# XMICRO-VDP_V1_0.net
KiCad netlist of a schematic drawn in EAGLE
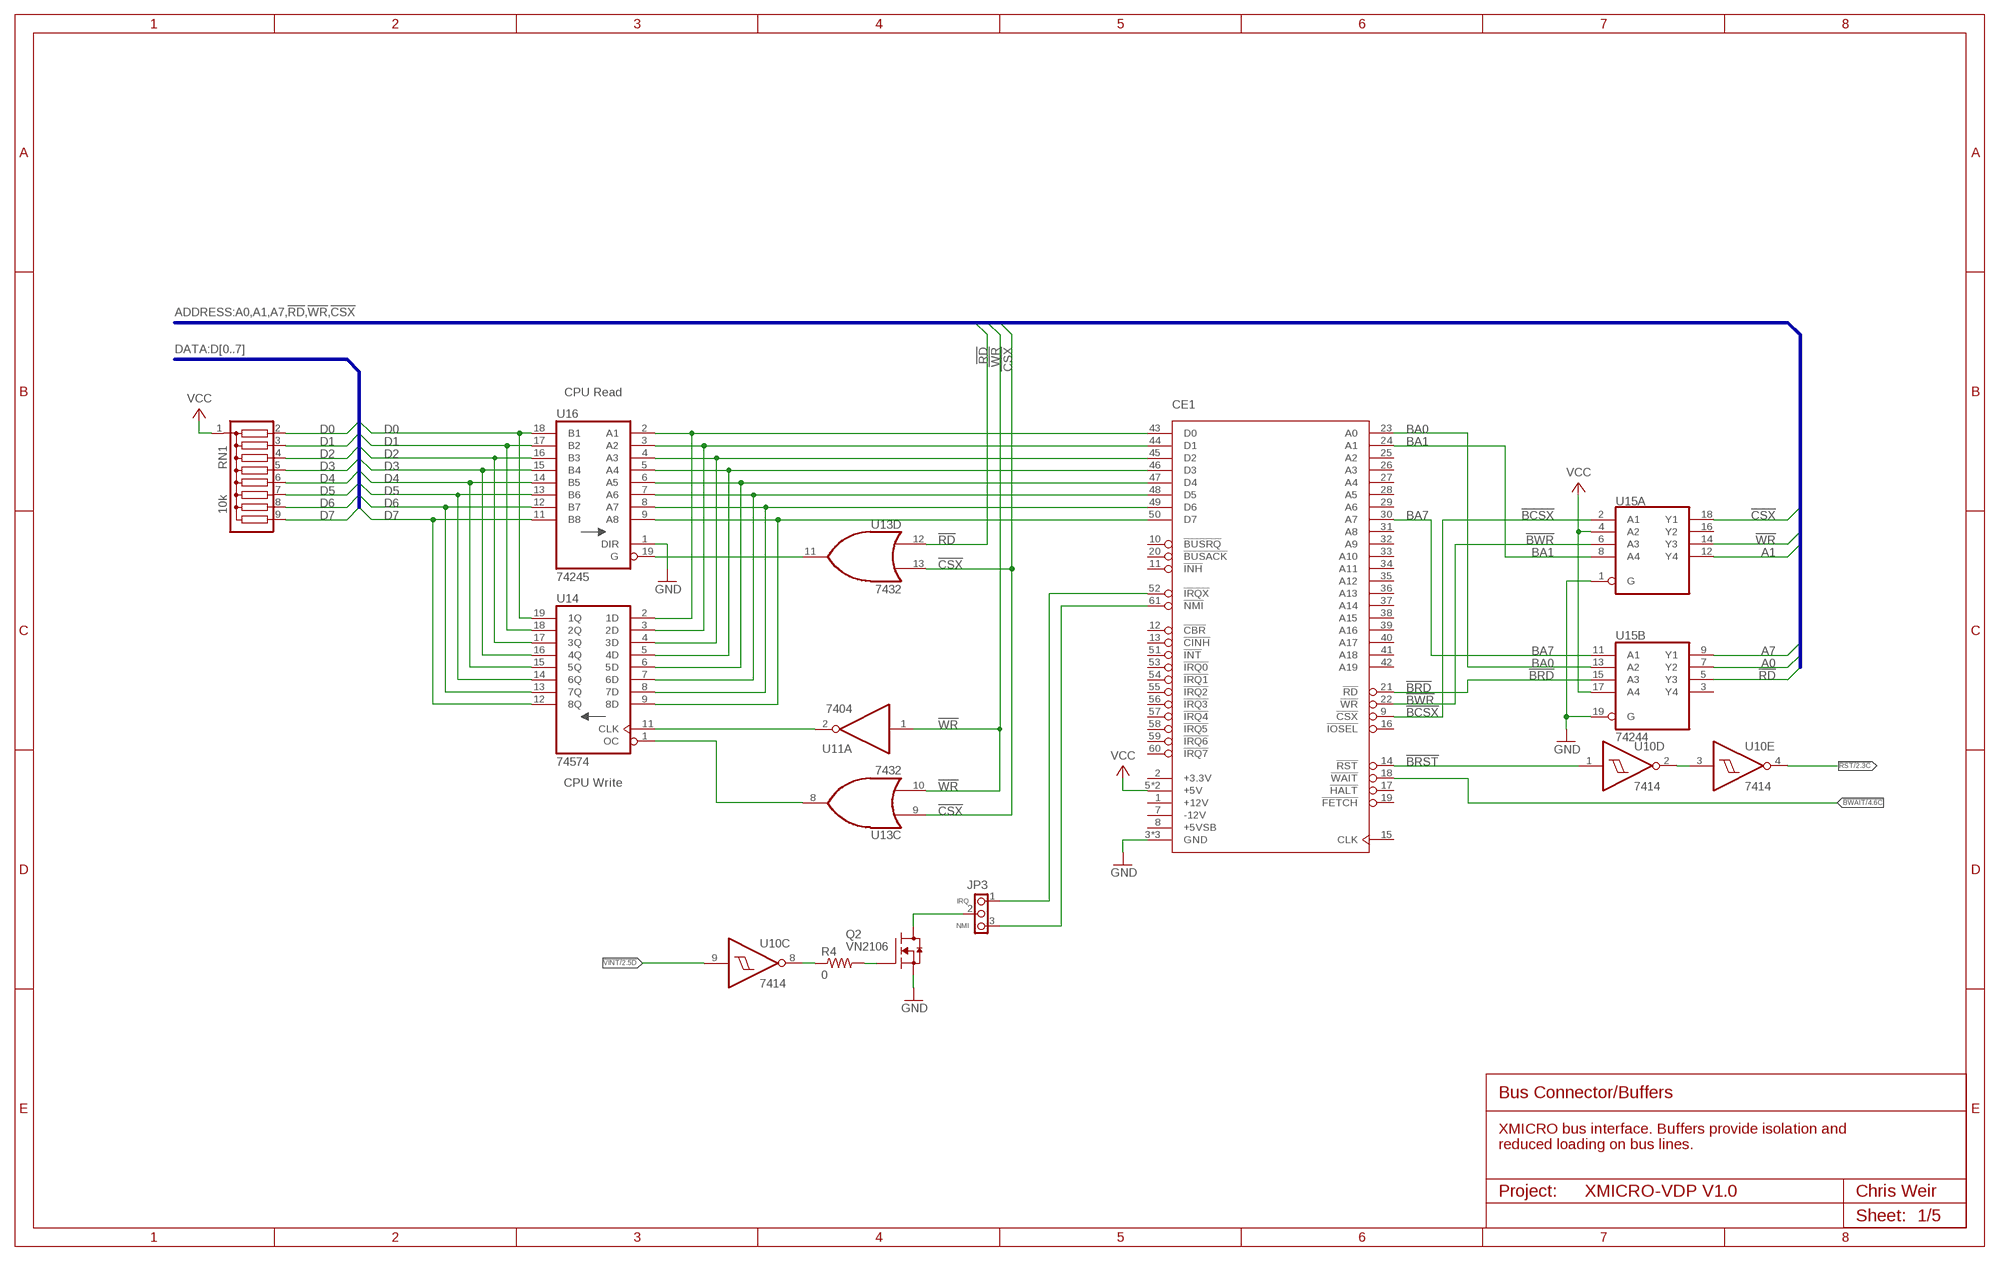
[diagram p0: schematic, sheet 1]
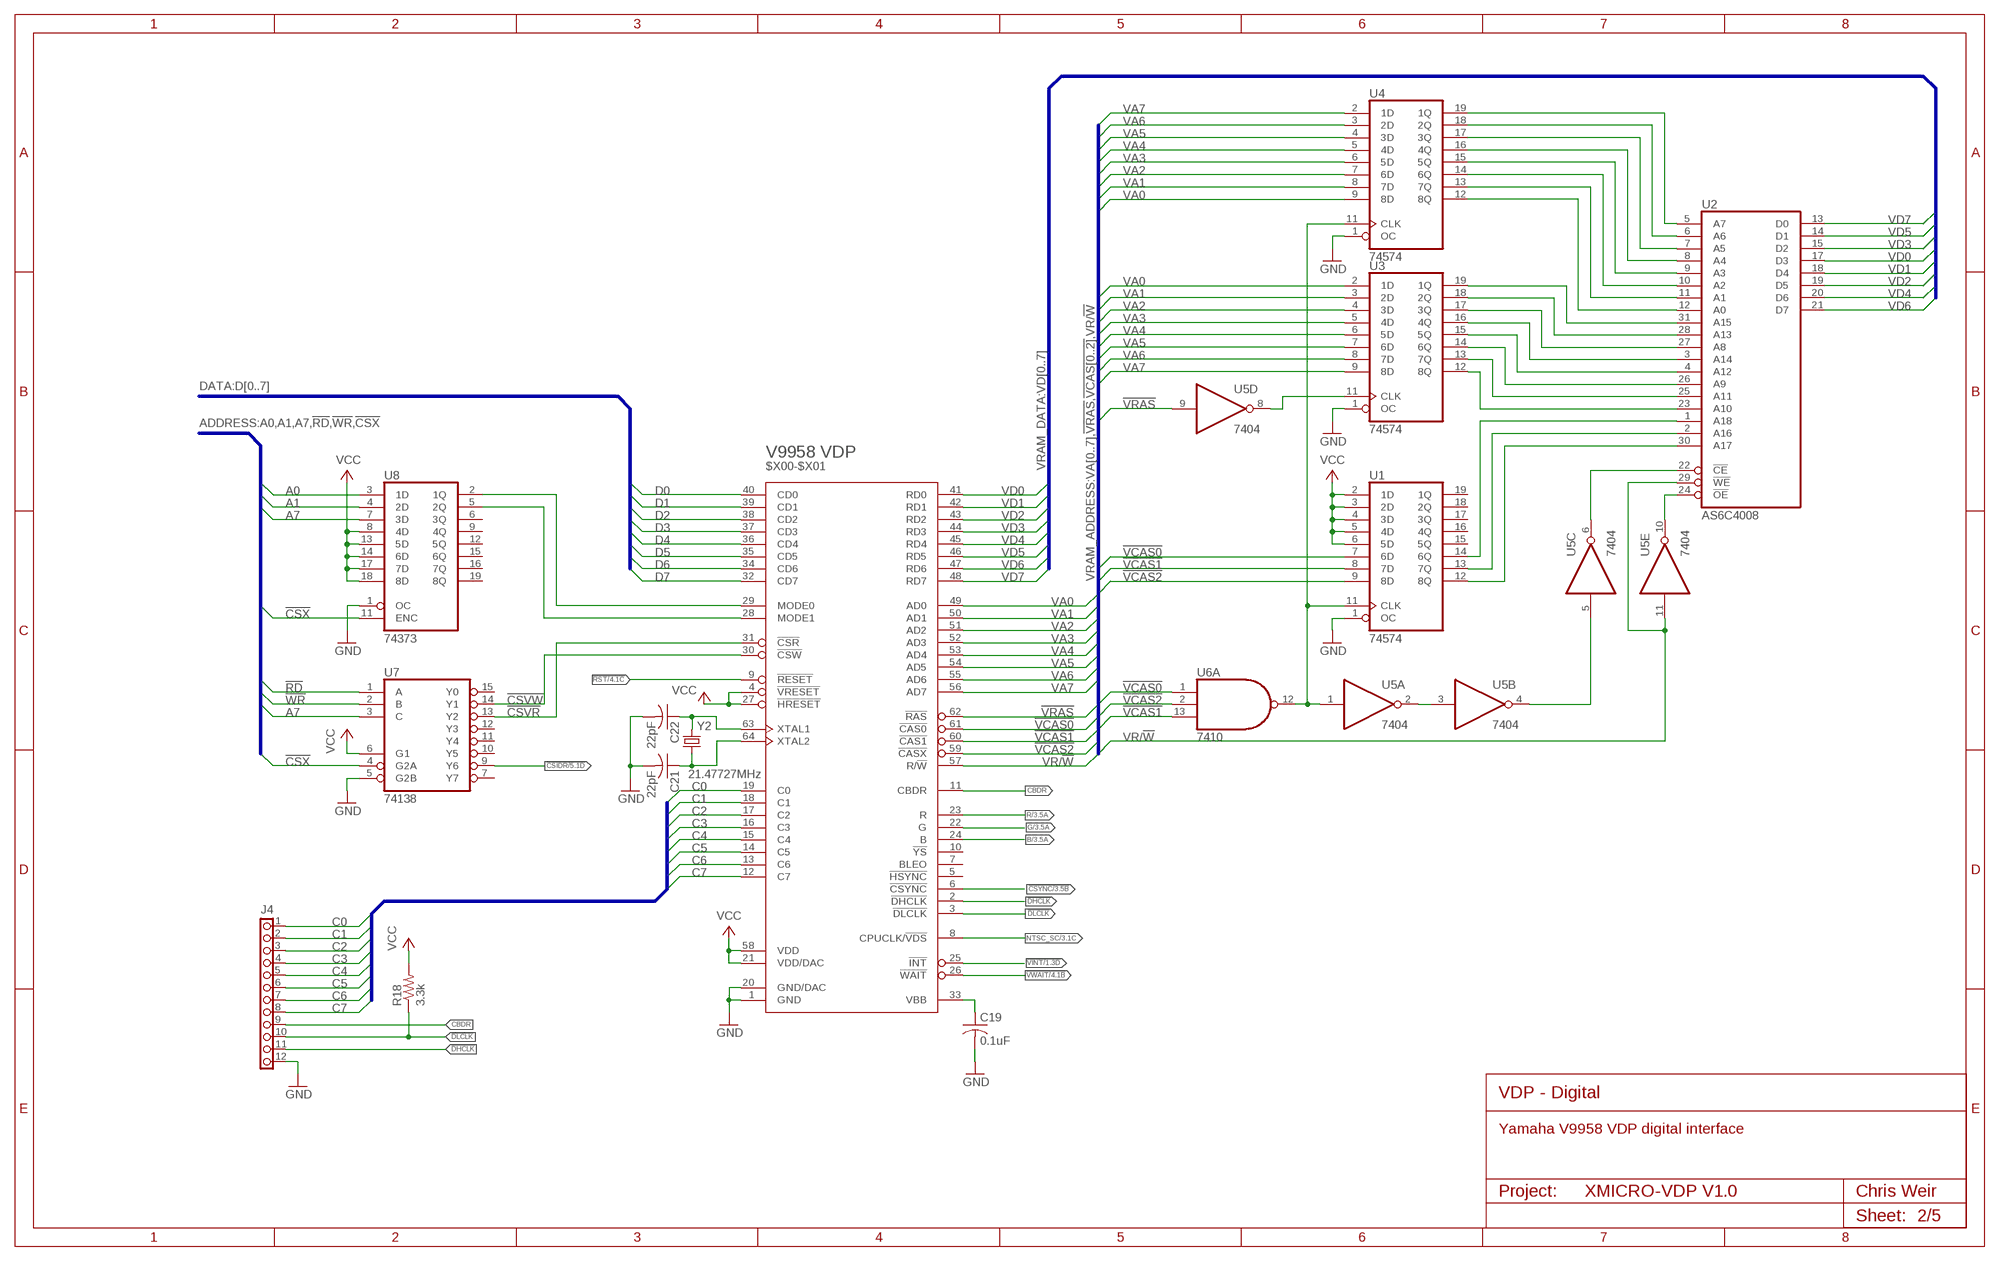
[diagram p1: schematic, sheet 2]
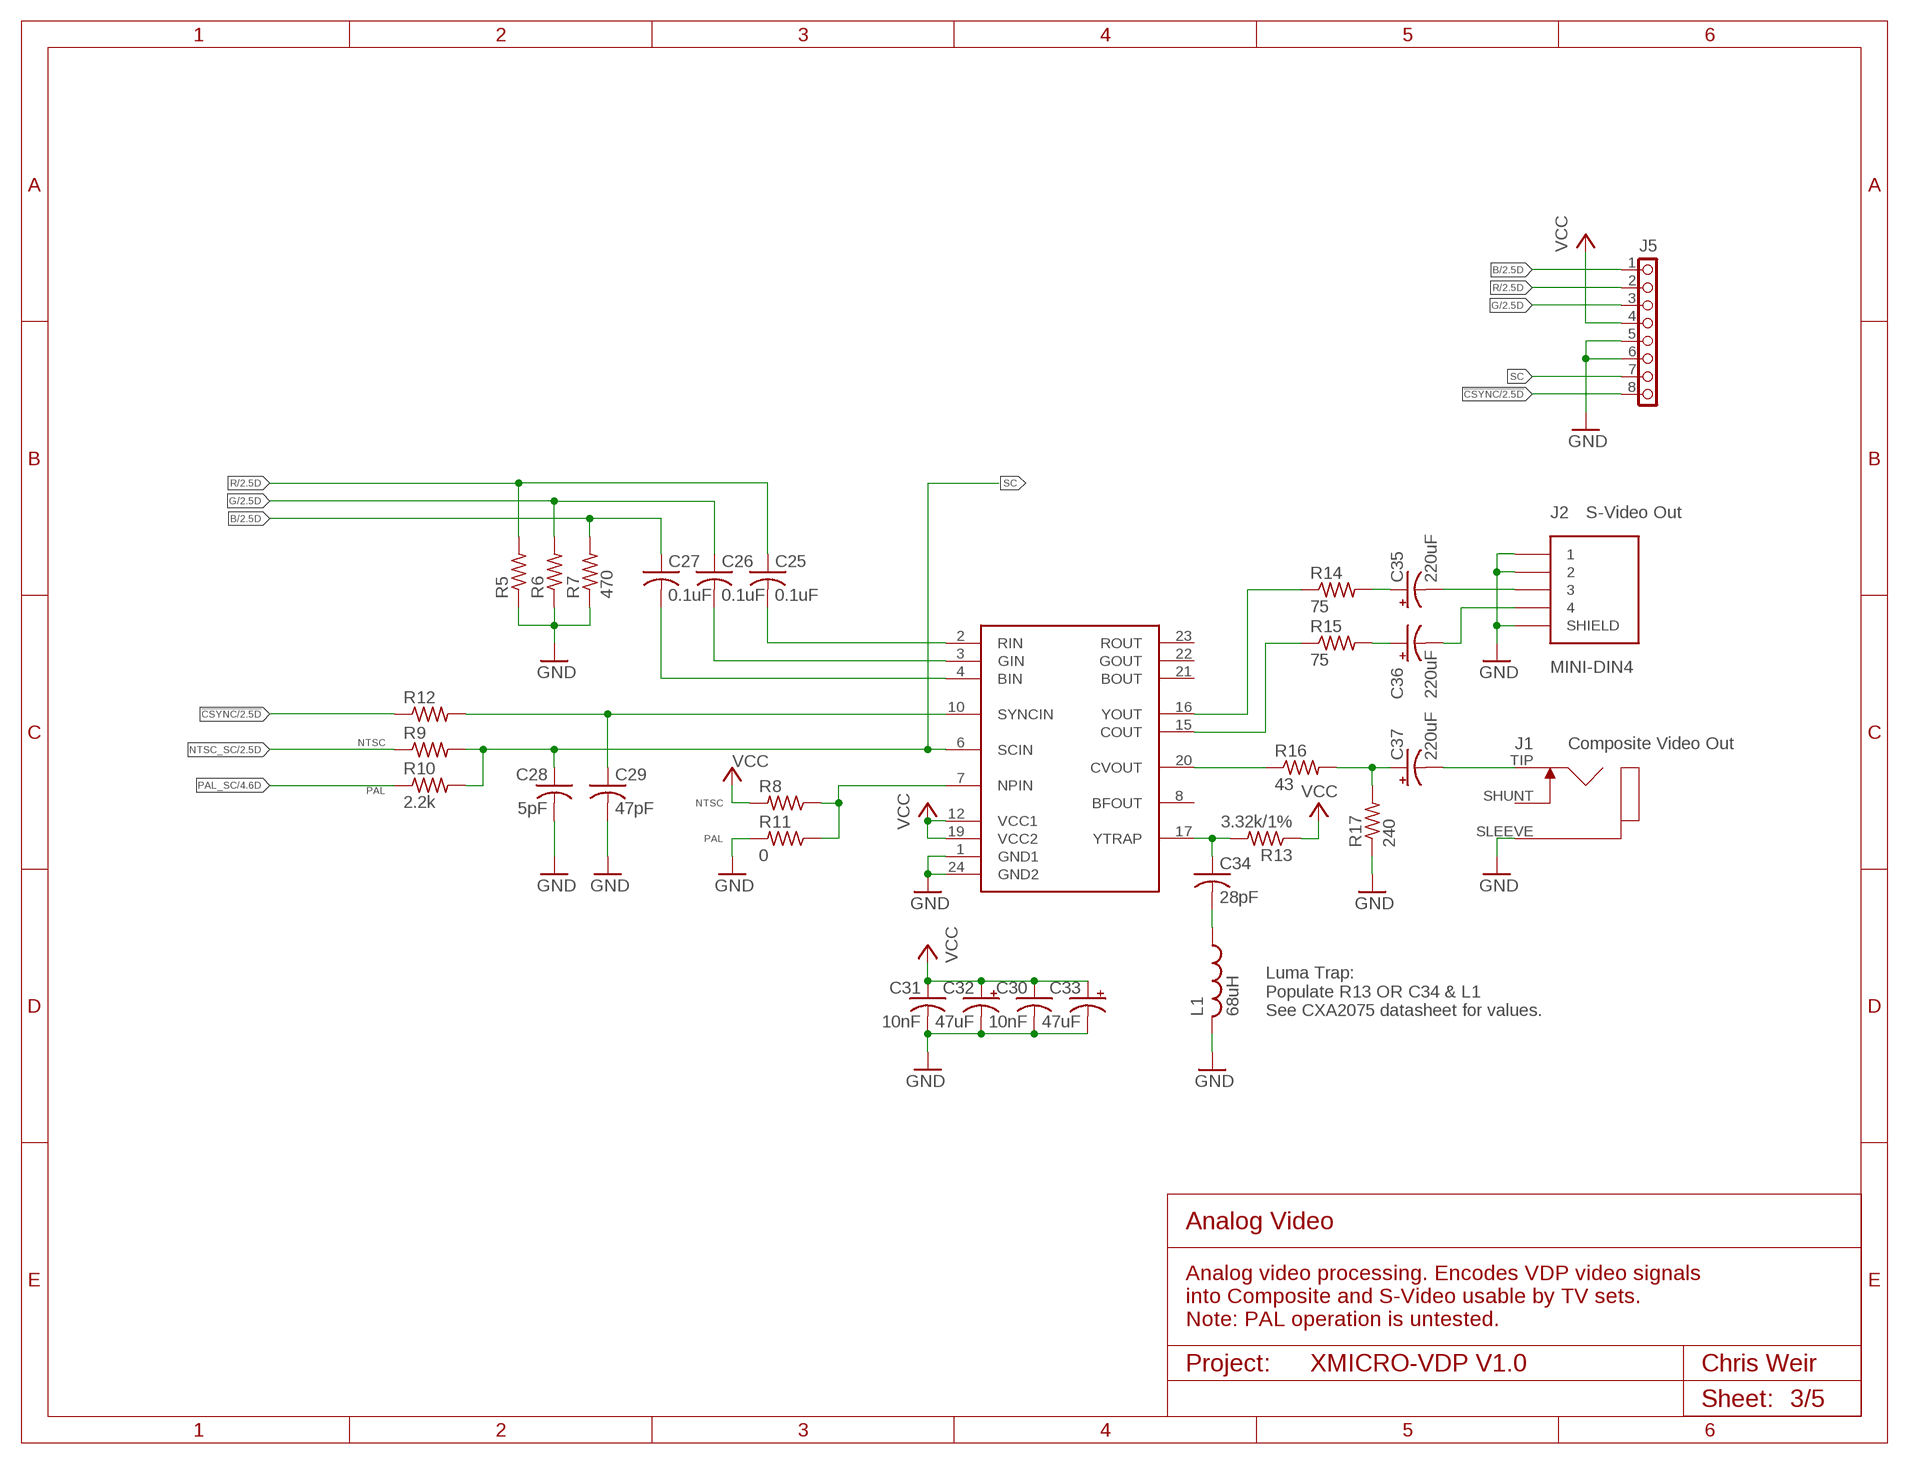
[diagram p2: schematic, sheet 3]
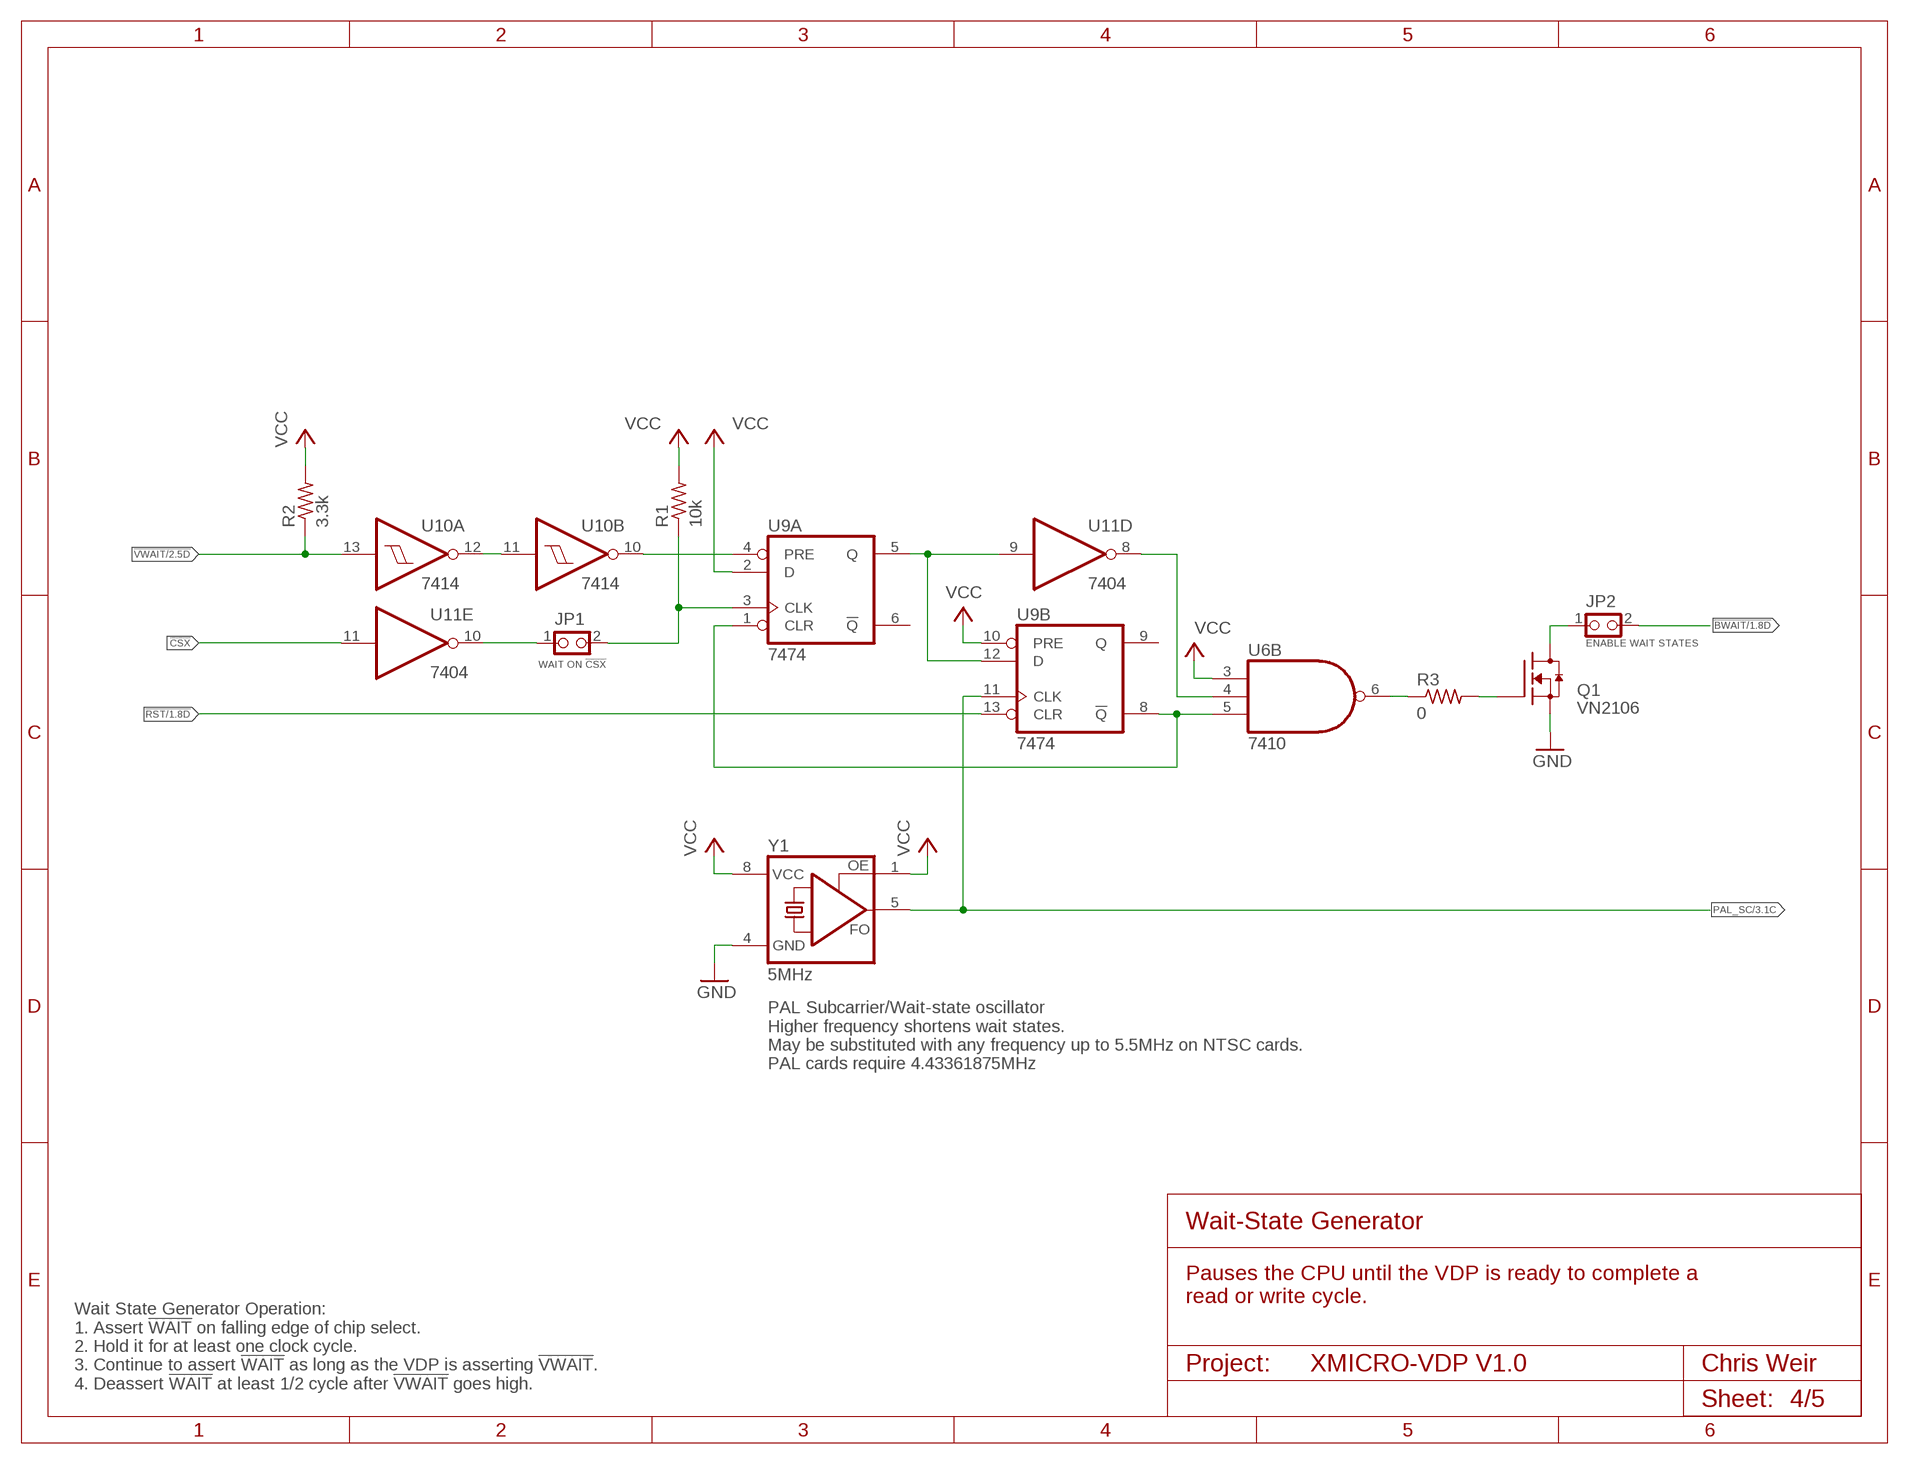
[diagram p3: schematic, sheet 4]
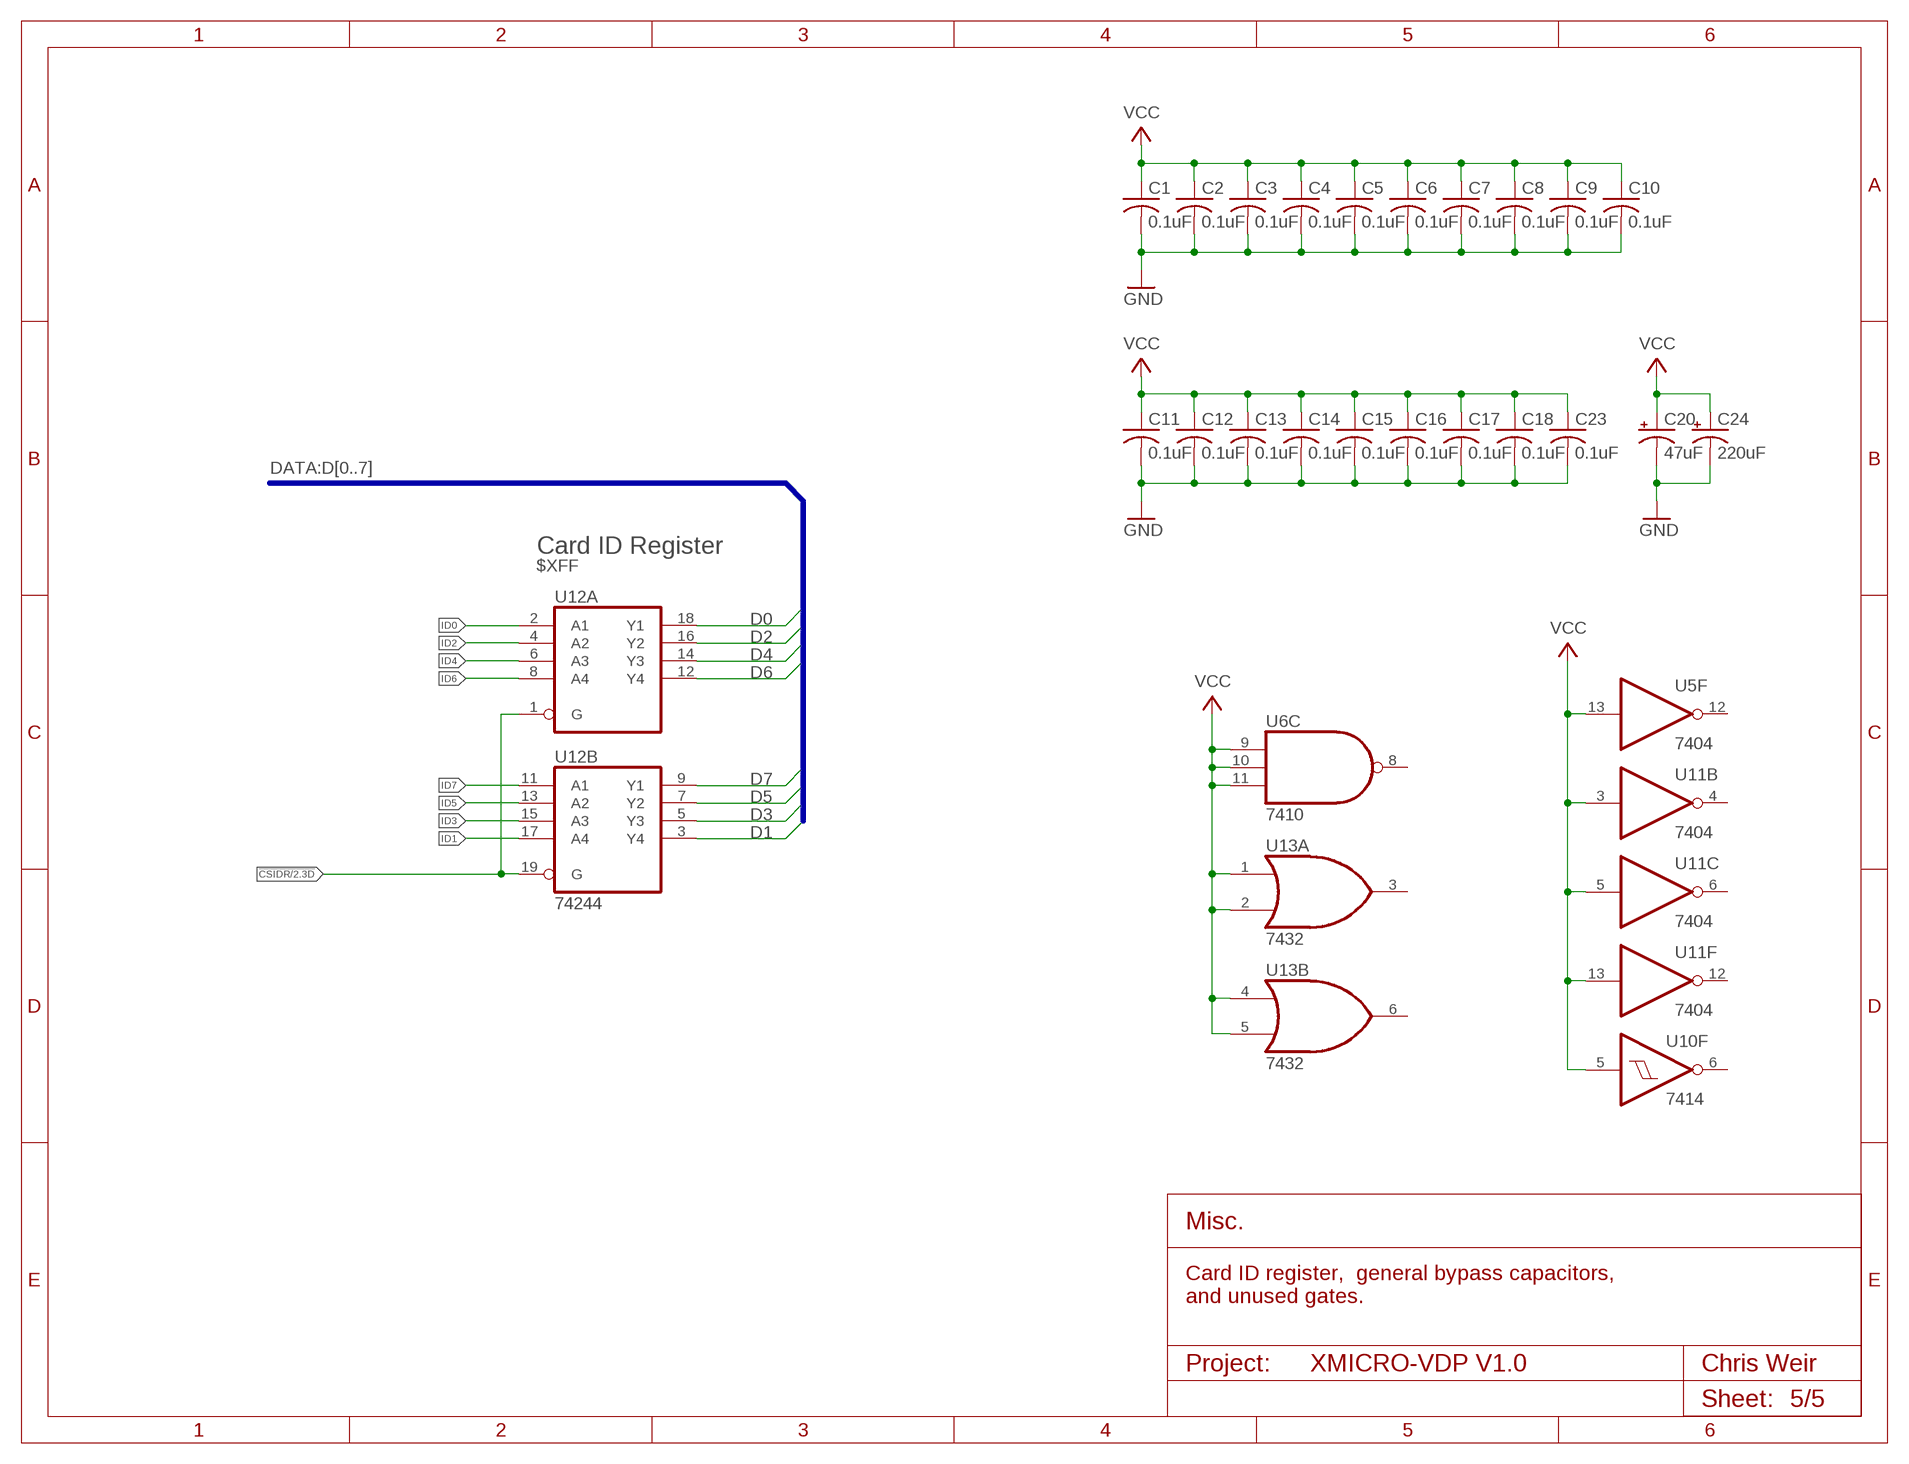
[diagram p4: schematic, sheet 5]

(export (version "E")
  (design (tool "Eeschema 10.0.6"))
  (components
    (comp (ref "JP1")
      (value "PINHD-1X2THRU")
      (footprint "eagle-import:1X02")
      (libsource (lib "eagle-import") (part "PINHD-1X2THRU"))
    )
    (comp (ref "JP2")
      (value "PINHD-1X2THRU")
      (footprint "eagle-import:1X02")
      (libsource (lib "eagle-import") (part "PINHD-1X2THRU"))
    )
    (comp (ref "Q1")
      (value "VN2106")
      (footprint "eagle-import:TO92")
      (libsource (lib "eagle-import") (part "VN2106"))
    )
    (comp (ref "R1")
      (value "10k")
      (footprint "eagle-import:0207_10")
      (libsource (lib "eagle-import") (part "R-US_0207/10"))
    )
    (comp (ref "R2")
      (value "3.3k")
      (footprint "eagle-import:0207_10")
      (libsource (lib "eagle-import") (part "R-US_0207/10"))
    )
    (comp (ref "R3")
      (value "0")
      (footprint "eagle-import:0207_10")
      (libsource (lib "eagle-import") (part "R-US_0207/10"))
    )
    (comp (ref "U6")
      (value "7410")
      (footprint "eagle-import:DIL14")
      (libsource (lib "eagle-import") (part "7410NLS"))
    )
    (comp (ref "U9")
      (value "7474")
      (footprint "eagle-import:DIL14")
      (libsource (lib "eagle-import") (part "7474NLS"))
    )
    (comp (ref "U10")
      (value "7414")
      (footprint "eagle-import:DIL14")
      (libsource (lib "eagle-import") (part "7414NLS"))
    )
    (comp (ref "U11")
      (value "7404")
      (footprint "eagle-import:DIL14")
      (libsource (lib "eagle-import") (part "7404NLS"))
    )
    (comp (ref "Y1")
      (value "5MHz")
      (footprint "eagle-import:DIL08S")
      (libsource (lib "eagle-import") (part "OSC-OE"))
    )
    (comp (ref "C19")
      (value "0.1uF")
      (footprint "eagle-import:C100")
      (libsource (lib "eagle-import") (part "C-US100"))
    )
    (comp (ref "C21")
      (value "22pF")
      (footprint "eagle-import:C100")
      (libsource (lib "eagle-import") (part "C-US100"))
    )
    (comp (ref "C22")
      (value "22pF")
      (footprint "eagle-import:C100")
      (libsource (lib "eagle-import") (part "C-US100"))
    )
    (comp (ref "J4")
      (value "PINHD-2X6")
      (footprint "eagle-import:2X06")
      (libsource (lib "eagle-import") (part "PINHD-2X6"))
    )
    (comp (ref "R18")
      (value "3.3k")
      (footprint "eagle-import:0207_10")
      (libsource (lib "eagle-import") (part "R-US_0207/10"))
    )
    (comp (ref "U1")
      (value "74574")
      (footprint "eagle-import:DIL20")
      (libsource (lib "eagle-import") (part "74574NHC"))
    )
    (comp (ref "U2")
      (value "AS6C4008")
      (footprint "eagle-import:DIL32-6")
      (libsource (lib "eagle-import") (part "4008-VDP"))
    )
    (comp (ref "U3")
      (value "74574")
      (footprint "eagle-import:DIL20")
      (libsource (lib "eagle-import") (part "74574NHC"))
    )
    (comp (ref "U4")
      (value "74574")
      (footprint "eagle-import:DIL20")
      (libsource (lib "eagle-import") (part "74574NHC"))
    )
    (comp (ref "U5")
      (value "7404")
      (footprint "eagle-import:DIL14")
      (libsource (lib "eagle-import") (part "7404NLS"))
    )
    (comp (ref "U7")
      (value "74138")
      (footprint "eagle-import:DIL16")
      (libsource (lib "eagle-import") (part "74138NS"))
    )
    (comp (ref "U8")
      (value "74373")
      (footprint "eagle-import:DIL20")
      (libsource (lib "eagle-import") (part "74373NLS"))
    )
    (comp (ref "U17")
      (value "V9958")
      (footprint "eagle-import:SDIP64")
      (libsource (lib "eagle-import") (part "V9958"))
    )
    (comp (ref "Y2")
      (value "21.47727MHz")
      (footprint "eagle-import:HC-49US")
      (libsource (lib "eagle-import") (part "CRYSTAL"))
    )
    (comp (ref "C1")
      (value "0.1uF")
      (footprint "eagle-import:C100")
      (libsource (lib "eagle-import") (part "C-US100"))
    )
    (comp (ref "C2")
      (value "0.1uF")
      (footprint "eagle-import:C100")
      (libsource (lib "eagle-import") (part "C-US100"))
    )
    (comp (ref "C3")
      (value "0.1uF")
      (footprint "eagle-import:C100")
      (libsource (lib "eagle-import") (part "C-US100"))
    )
    (comp (ref "C4")
      (value "0.1uF")
      (footprint "eagle-import:C100")
      (libsource (lib "eagle-import") (part "C-US100"))
    )
    (comp (ref "C5")
      (value "0.1uF")
      (footprint "eagle-import:C100")
      (libsource (lib "eagle-import") (part "C-US100"))
    )
    (comp (ref "C6")
      (value "0.1uF")
      (footprint "eagle-import:C100")
      (libsource (lib "eagle-import") (part "C-US100"))
    )
    (comp (ref "C7")
      (value "0.1uF")
      (footprint "eagle-import:C100")
      (libsource (lib "eagle-import") (part "C-US100"))
    )
    (comp (ref "C8")
      (value "0.1uF")
      (footprint "eagle-import:C100")
      (libsource (lib "eagle-import") (part "C-US100"))
    )
    (comp (ref "C9")
      (value "0.1uF")
      (footprint "eagle-import:C100")
      (libsource (lib "eagle-import") (part "C-US100"))
    )
    (comp (ref "C10")
      (value "0.1uF")
      (footprint "eagle-import:C100")
      (libsource (lib "eagle-import") (part "C-US100"))
    )
    (comp (ref "C11")
      (value "0.1uF")
      (footprint "eagle-import:C100")
      (libsource (lib "eagle-import") (part "C-US100"))
    )
    (comp (ref "C12")
      (value "0.1uF")
      (footprint "eagle-import:C100")
      (libsource (lib "eagle-import") (part "C-US100"))
    )
    (comp (ref "C13")
      (value "0.1uF")
      (footprint "eagle-import:C100")
      (libsource (lib "eagle-import") (part "C-US100"))
    )
    (comp (ref "C14")
      (value "0.1uF")
      (footprint "eagle-import:C100")
      (libsource (lib "eagle-import") (part "C-US100"))
    )
    (comp (ref "C15")
      (value "0.1uF")
      (footprint "eagle-import:C100")
      (libsource (lib "eagle-import") (part "C-US100"))
    )
    (comp (ref "C16")
      (value "0.1uF")
      (footprint "eagle-import:C100")
      (libsource (lib "eagle-import") (part "C-US100"))
    )
    (comp (ref "C17")
      (value "0.1uF")
      (footprint "eagle-import:C100")
      (libsource (lib "eagle-import") (part "C-US100"))
    )
    (comp (ref "C18")
      (value "0.1uF")
      (footprint "eagle-import:C100")
      (libsource (lib "eagle-import") (part "C-US100"))
    )
    (comp (ref "C20")
      (value "47uF")
      (footprint "eagle-import:E2,5-6")
      (libsource (lib "eagle-import") (part "CPOL-USE2.5-6"))
    )
    (comp (ref "C23")
      (value "0.1uF")
      (footprint "eagle-import:C100")
      (libsource (lib "eagle-import") (part "C-US100"))
    )
    (comp (ref "C24")
      (value "220uF")
      (footprint "eagle-import:C-10-5")
      (libsource (lib "eagle-import") (part "CPOL-US-10-5"))
    )
    (comp (ref "U12")
      (value "74244")
      (footprint "eagle-import:DIL20")
      (libsource (lib "eagle-import") (part "74244NLS"))
    )
    (comp (ref "U13")
      (value "7432")
      (footprint "eagle-import:DIL14")
      (libsource (lib "eagle-import") (part "7432NLS"))
    )
    (comp (ref "C25")
      (value "0.1uF")
      (footprint "eagle-import:C100")
      (libsource (lib "eagle-import") (part "C-US100"))
    )
    (comp (ref "C26")
      (value "0.1uF")
      (footprint "eagle-import:C100")
      (libsource (lib "eagle-import") (part "C-US100"))
    )
    (comp (ref "C27")
      (value "0.1uF")
      (footprint "eagle-import:C100")
      (libsource (lib "eagle-import") (part "C-US100"))
    )
    (comp (ref "C28")
      (value "5pF")
      (footprint "eagle-import:C100")
      (libsource (lib "eagle-import") (part "C-US100"))
    )
    (comp (ref "C29")
      (value "47pF")
      (footprint "eagle-import:C100")
      (libsource (lib "eagle-import") (part "C-US100"))
    )
    (comp (ref "C30")
      (value "10nF")
      (footprint "eagle-import:C100")
      (libsource (lib "eagle-import") (part "C-US100"))
    )
    (comp (ref "C31")
      (value "10nF")
      (footprint "eagle-import:C100")
      (libsource (lib "eagle-import") (part "C-US100"))
    )
    (comp (ref "C32")
      (value "47uF")
      (footprint "eagle-import:E2,5-6")
      (libsource (lib "eagle-import") (part "CPOL-USE2.5-6"))
    )
    (comp (ref "C33")
      (value "47uF")
      (footprint "eagle-import:E2,5-6")
      (libsource (lib "eagle-import") (part "CPOL-USE2.5-6"))
    )
    (comp (ref "C34")
      (value "28pF")
      (footprint "eagle-import:C100")
      (libsource (lib "eagle-import") (part "C-US100"))
    )
    (comp (ref "C35")
      (value "220uF")
      (footprint "eagle-import:E2,5-6")
      (libsource (lib "eagle-import") (part "CPOL-USE2.5-6"))
    )
    (comp (ref "C36")
      (value "220uF")
      (footprint "eagle-import:E2,5-6")
      (libsource (lib "eagle-import") (part "CPOL-USE2.5-6"))
    )
    (comp (ref "C37")
      (value "220uF")
      (footprint "eagle-import:E2,5-6")
      (libsource (lib "eagle-import") (part "CPOL-USE2.5-6"))
    )
    (comp (ref "J1")
      (value "PJRAN1XU04AUX")
      (footprint "eagle-import:PJRAN1")
      (libsource (lib "eagle-import") (part "PJRAN1"))
    )
    (comp (ref "J2")
      (value "MINI-DIN4")
      (footprint "eagle-import:MINI-DIN4")
      (libsource (lib "eagle-import") (part "MINI-DIN4"))
    )
    (comp (ref "J5")
      (value "PINHD-1X8")
      (footprint "eagle-import:1X08")
      (libsource (lib "eagle-import") (part "PINHD-1X8"))
    )
    (comp (ref "L1")
      (value "68uH")
      (footprint "eagle-import:0204V")
      (libsource (lib "eagle-import") (part "L-US0204V"))
    )
    (comp (ref "R5")
      (value "470")
      (footprint "eagle-import:0207_10")
      (libsource (lib "eagle-import") (part "R-US_0207/10"))
    )
    (comp (ref "R6")
      (value "470")
      (footprint "eagle-import:0207_10")
      (libsource (lib "eagle-import") (part "R-US_0207/10"))
    )
    (comp (ref "R7")
      (value "470")
      (footprint "eagle-import:0207_10")
      (libsource (lib "eagle-import") (part "R-US_0207/10"))
    )
    (comp (ref "R8")
      (value "0")
      (footprint "eagle-import:0207_10")
      (libsource (lib "eagle-import") (part "R-US_0207/10"))
    )
    (comp (ref "R9")
      (value "2.2k")
      (footprint "eagle-import:0207_10")
      (libsource (lib "eagle-import") (part "R-US_0207/10"))
    )
    (comp (ref "R10")
      (value "2.2k")
      (footprint "eagle-import:0207_10")
      (libsource (lib "eagle-import") (part "R-US_0207/10"))
    )
    (comp (ref "R11")
      (value "0")
      (footprint "eagle-import:0207_10")
      (libsource (lib "eagle-import") (part "R-US_0207/10"))
    )
    (comp (ref "R12")
      (value "2.2k")
      (footprint "eagle-import:0207_10")
      (libsource (lib "eagle-import") (part "R-US_0207/10"))
    )
    (comp (ref "R13")
      (value "3.32k/1%")
      (footprint "eagle-import:0207_10")
      (libsource (lib "eagle-import") (part "R-US_0207/10"))
    )
    (comp (ref "R14")
      (value "75")
      (footprint "eagle-import:0207_10")
      (libsource (lib "eagle-import") (part "R-US_0207/10"))
    )
    (comp (ref "R15")
      (value "75")
      (footprint "eagle-import:0207_10")
      (libsource (lib "eagle-import") (part "R-US_0207/10"))
    )
    (comp (ref "R16")
      (value "43")
      (footprint "eagle-import:0207_10")
      (libsource (lib "eagle-import") (part "R-US_0207/10"))
    )
    (comp (ref "R17")
      (value "240")
      (footprint "eagle-import:0207_10")
      (libsource (lib "eagle-import") (part "R-US_0207/10"))
    )
    (comp (ref "U18")
      (value "CXA2075")
      (footprint "eagle-import:SOP-24")
      (libsource (lib "eagle-import") (part "CXA2075"))
    )
    (comp (ref "CE1")
      (value "XMICRO-BUS-EDGE62M")
      (footprint "eagle-import:EDGE62M")
      (libsource (lib "eagle-import") (part "XMICRO-BUS-EDGE62M"))
    )
    (comp (ref "JP3")
      (value "PINHD1X3THRU")
      (footprint "eagle-import:1X03")
      (libsource (lib "eagle-import") (part "PINHD1X3THRU"))
    )
    (comp (ref "Q2")
      (value "VN2106")
      (footprint "eagle-import:TO92")
      (libsource (lib "eagle-import") (part "VN2106"))
    )
    (comp (ref "R4")
      (value "0")
      (footprint "eagle-import:0207_10")
      (libsource (lib "eagle-import") (part "R-US_0207/10"))
    )
    (comp (ref "RN1")
      (value "10k")
      (footprint "eagle-import:SIL9")
      (libsource (lib "eagle-import") (part "RN8"))
    )
    (comp (ref "U14")
      (value "74574")
      (footprint "eagle-import:DIL20")
      (libsource (lib "eagle-import") (part "74574NHC"))
    )
    (comp (ref "U15")
      (value "74244")
      (footprint "eagle-import:DIL20")
      (libsource (lib "eagle-import") (part "74244NLS"))
    )
    (comp (ref "U16")
      (value "74245")
      (footprint "eagle-import:DIL20")
      (libsource (lib "eagle-import") (part "74245NLS"))
    )
  )
  (nets
    (net (code "42") (name "A0") (class "Default")
      (node (ref "U15") (pin "7") (pinfunction "Y2_7") (pintype "tri_state"))
      (node (ref "U8") (pin "3") (pinfunction "1D_3") (pintype "input"))
    )
    (net (code "43") (name "A1") (class "Default")
      (node (ref "U15") (pin "12") (pinfunction "Y4_12") (pintype "tri_state"))
      (node (ref "U8") (pin "4") (pinfunction "2D_4") (pintype "input"))
    )
    (net (code "44") (name "A7") (class "Default")
      (node (ref "U15") (pin "9") (pinfunction "Y1_9") (pintype "tri_state"))
      (node (ref "U7") (pin "3") (pinfunction "C_3") (pintype "input"))
      (node (ref "U8") (pin "7") (pinfunction "3D_7") (pintype "input"))
    )
    (net (code "45") (name "B") (class "Default")
      (node (ref "C27") (pin "P$1") (pinfunction "1_P$1") (pintype "passive"))
      (node (ref "J5") (pin "1") (pinfunction "1_1") (pintype "passive"))
      (node (ref "R7") (pin "2") (pinfunction "2_2") (pintype "passive"))
      (node (ref "U17") (pin "24") (pinfunction "B_24") (pintype "output"))
    )
    (net (code "46") (name "BA0") (class "Default")
      (node (ref "CE1") (pin "23") (pinfunction "A0_23") (pintype "bidirectional"))
      (node (ref "U15") (pin "13") (pinfunction "A2_13") (pintype "input"))
    )
    (net (code "47") (name "BA1") (class "Default")
      (node (ref "CE1") (pin "24") (pinfunction "A1_24") (pintype "bidirectional"))
      (node (ref "U15") (pin "8") (pinfunction "A4_8") (pintype "input"))
    )
    (net (code "48") (name "BA7") (class "Default")
      (node (ref "CE1") (pin "30") (pinfunction "A7_30") (pintype "bidirectional"))
      (node (ref "U15") (pin "11") (pinfunction "A1_11") (pintype "input"))
    )
    (net (code "49") (name "C0") (class "Default")
      (node (ref "J4") (pin "1") (pinfunction "1_1") (pintype "passive"))
      (node (ref "U17") (pin "19") (pinfunction "C0_19") (pintype "bidirectional"))
    )
    (net (code "50") (name "C1") (class "Default")
      (node (ref "J4") (pin "2") (pinfunction "2_2") (pintype "passive"))
      (node (ref "U17") (pin "18") (pinfunction "C1_18") (pintype "bidirectional"))
    )
    (net (code "51") (name "C2") (class "Default")
      (node (ref "J4") (pin "3") (pinfunction "3_3") (pintype "passive"))
      (node (ref "U17") (pin "17") (pinfunction "C2_17") (pintype "bidirectional"))
    )
    (net (code "52") (name "C3") (class "Default")
      (node (ref "J4") (pin "4") (pinfunction "4_4") (pintype "passive"))
      (node (ref "U17") (pin "16") (pinfunction "C3_16") (pintype "bidirectional"))
    )
    (net (code "53") (name "C4") (class "Default")
      (node (ref "J4") (pin "5") (pinfunction "5_5") (pintype "passive"))
      (node (ref "U17") (pin "15") (pinfunction "C4_15") (pintype "bidirectional"))
    )
    (net (code "54") (name "C5") (class "Default")
      (node (ref "J4") (pin "6") (pinfunction "6_6") (pintype "passive"))
      (node (ref "U17") (pin "14") (pinfunction "C5_14") (pintype "bidirectional"))
    )
    (net (code "55") (name "C6") (class "Default")
      (node (ref "J4") (pin "7") (pinfunction "7_7") (pintype "passive"))
      (node (ref "U17") (pin "13") (pinfunction "C6_13") (pintype "bidirectional"))
    )
    (net (code "56") (name "C7") (class "Default")
      (node (ref "J4") (pin "8") (pinfunction "8_8") (pintype "passive"))
      (node (ref "U17") (pin "12") (pinfunction "C7_12") (pintype "bidirectional"))
    )
    (net (code "57") (name "CBDR") (class "Default")
      (node (ref "J4") (pin "9") (pinfunction "9_9") (pintype "passive"))
      (node (ref "U17") (pin "11") (pinfunction "CBDR_11") (pintype "output"))
    )
    (net (code "58") (name "D0") (class "Default")
      (node (ref "RN1") (pin "2") (pinfunction "2_2") (pintype "passive"))
      (node (ref "U12") (pin "18") (pinfunction "Y1_18") (pintype "tri_state"))
      (node (ref "U14") (pin "19") (pinfunction "1Q_19") (pintype "tri_state"))
      (node (ref "U16") (pin "18") (pinfunction "B1_18") (pintype "bidirectional"))
      (node (ref "U17") (pin "40") (pinfunction "CD0_40") (pintype "bidirectional"))
    )
    (net (code "59") (name "D1") (class "Default")
      (node (ref "RN1") (pin "3") (pinfunction "3_3") (pintype "passive"))
      (node (ref "U12") (pin "3") (pinfunction "Y4_3") (pintype "tri_state"))
      (node (ref "U14") (pin "18") (pinfunction "2Q_18") (pintype "tri_state"))
      (node (ref "U16") (pin "17") (pinfunction "B2_17") (pintype "bidirectional"))
      (node (ref "U17") (pin "39") (pinfunction "CD1_39") (pintype "bidirectional"))
    )
    (net (code "60") (name "D2") (class "Default")
      (node (ref "RN1") (pin "4") (pinfunction "4_4") (pintype "passive"))
      (node (ref "U12") (pin "16") (pinfunction "Y2_16") (pintype "tri_state"))
      (node (ref "U14") (pin "17") (pinfunction "3Q_17") (pintype "tri_state"))
      (node (ref "U16") (pin "16") (pinfunction "B3_16") (pintype "bidirectional"))
      (node (ref "U17") (pin "38") (pinfunction "CD2_38") (pintype "bidirectional"))
    )
    (net (code "61") (name "D3") (class "Default")
      (node (ref "RN1") (pin "5") (pinfunction "5_5") (pintype "passive"))
      (node (ref "U12") (pin "5") (pinfunction "Y3_5") (pintype "tri_state"))
      (node (ref "U14") (pin "16") (pinfunction "4Q_16") (pintype "tri_state"))
      (node (ref "U16") (pin "15") (pinfunction "B4_15") (pintype "bidirectional"))
      (node (ref "U17") (pin "37") (pinfunction "CD3_37") (pintype "bidirectional"))
    )
    (net (code "62") (name "D4") (class "Default")
      (node (ref "RN1") (pin "6") (pinfunction "6_6") (pintype "passive"))
      (node (ref "U12") (pin "14") (pinfunction "Y3_14") (pintype "tri_state"))
      (node (ref "U14") (pin "15") (pinfunction "5Q_15") (pintype "tri_state"))
      (node (ref "U16") (pin "14") (pinfunction "B5_14") (pintype "bidirectional"))
      (node (ref "U17") (pin "36") (pinfunction "CD4_36") (pintype "bidirectional"))
    )
    (net (code "63") (name "D5") (class "Default")
      (node (ref "RN1") (pin "7") (pinfunction "7_7") (pintype "passive"))
      (node (ref "U12") (pin "7") (pinfunction "Y2_7") (pintype "tri_state"))
      (node (ref "U14") (pin "14") (pinfunction "6Q_14") (pintype "tri_state"))
      (node (ref "U16") (pin "13") (pinfunction "B6_13") (pintype "bidirectional"))
      (node (ref "U17") (pin "35") (pinfunction "CD5_35") (pintype "bidirectional"))
    )
    (net (code "64") (name "D6") (class "Default")
      (node (ref "RN1") (pin "8") (pinfunction "8_8") (pintype "passive"))
      (node (ref "U12") (pin "12") (pinfunction "Y4_12") (pintype "tri_state"))
      (node (ref "U14") (pin "13") (pinfunction "7Q_13") (pintype "tri_state"))
      (node (ref "U16") (pin "12") (pinfunction "B7_12") (pintype "bidirectional"))
      (node (ref "U17") (pin "34") (pinfunction "CD6_34") (pintype "bidirectional"))
    )
    (net (code "65") (name "D7") (class "Default")
      (node (ref "RN1") (pin "9") (pinfunction "9_9") (pintype "passive"))
      (node (ref "U12") (pin "9") (pinfunction "Y1_9") (pintype "tri_state"))
      (node (ref "U14") (pin "12") (pinfunction "8Q_12") (pintype "tri_state"))
      (node (ref "U16") (pin "11") (pinfunction "B8_11") (pintype "bidirectional"))
      (node (ref "U17") (pin "32") (pinfunction "CD7_32") (pintype "bidirectional"))
    )
    (net (code "66") (name "G") (class "Default")
      (node (ref "C26") (pin "P$1") (pinfunction "1_P$1") (pintype "passive"))
      (node (ref "J5") (pin "3") (pinfunction "3_3") (pintype "passive"))
      (node (ref "R6") (pin "2") (pinfunction "2_2") (pintype "passive"))
      (node (ref "U17") (pin "22") (pinfunction "G_22") (pintype "output"))
    )
    (net (code "67") (name "GND") (class "Default")
      (node (ref "C1") (pin "P$2") (pinfunction "2_P$2") (pintype "passive"))
      (node (ref "C10") (pin "P$2") (pinfunction "2_P$2") (pintype "passive"))
      (node (ref "C11") (pin "P$2") (pinfunction "2_P$2") (pintype "passive"))
      (node (ref "C12") (pin "P$2") (pinfunction "2_P$2") (pintype "passive"))
      (node (ref "C13") (pin "P$2") (pinfunction "2_P$2") (pintype "passive"))
      (node (ref "C14") (pin "P$2") (pinfunction "2_P$2") (pintype "passive"))
      (node (ref "C15") (pin "P$2") (pinfunction "2_P$2") (pintype "passive"))
      (node (ref "C16") (pin "P$2") (pinfunction "2_P$2") (pintype "passive"))
      (node (ref "C17") (pin "P$2") (pinfunction "2_P$2") (pintype "passive"))
      (node (ref "C18") (pin "P$2") (pinfunction "2_P$2") (pintype "passive"))
      (node (ref "C19") (pin "P$2") (pinfunction "2_P$2") (pintype "passive"))
      (node (ref "C2") (pin "P$2") (pinfunction "2_P$2") (pintype "passive"))
      (node (ref "C20") (pin "-") (pinfunction "-_-") (pintype "passive"))
      (node (ref "C21") (pin "P$2") (pinfunction "2_P$2") (pintype "passive"))
      (node (ref "C22") (pin "P$2") (pinfunction "2_P$2") (pintype "passive"))
      (node (ref "C23") (pin "P$2") (pinfunction "2_P$2") (pintype "passive"))
      (node (ref "C24") (pin "-") (pinfunction "-_-") (pintype "passive"))
      (node (ref "C28") (pin "P$2") (pinfunction "2_P$2") (pintype "passive"))
      (node (ref "C29") (pin "P$2") (pinfunction "2_P$2") (pintype "passive"))
      (node (ref "C3") (pin "P$2") (pinfunction "2_P$2") (pintype "passive"))
      (node (ref "C30") (pin "P$2") (pinfunction "2_P$2") (pintype "passive"))
      (node (ref "C31") (pin "P$2") (pinfunction "2_P$2") (pintype "passive"))
      (node (ref "C32") (pin "-") (pinfunction "-_-") (pintype "passive"))
      (node (ref "C33") (pin "-") (pinfunction "-_-") (pintype "passive"))
      (node (ref "C4") (pin "P$2") (pinfunction "2_P$2") (pintype "passive"))
      (node (ref "C5") (pin "P$2") (pinfunction "2_P$2") (pintype "passive"))
      (node (ref "C6") (pin "P$2") (pinfunction "2_P$2") (pintype "passive"))
      (node (ref "C7") (pin "P$2") (pinfunction "2_P$2") (pintype "passive"))
      (node (ref "C8") (pin "P$2") (pinfunction "2_P$2") (pintype "passive"))
      (node (ref "C9") (pin "P$2") (pinfunction "2_P$2") (pintype "passive"))
      (node (ref "CE1") (pin "3") (pinfunction "GND_3") (pintype "bidirectional"))
      (node (ref "CE1") (pin "4") (pinfunction "GND_4") (pintype "bidirectional"))
      (node (ref "CE1") (pin "62") (pinfunction "GND_62") (pintype "bidirectional"))
      (node (ref "J1") (pin "SLEEVE") (pinfunction "SLEEVE_SLEEVE") (pintype "bidirectional"))
      (node (ref "J2") (pin "1") (pinfunction "1_1") (pintype "bidirectional"))
      (node (ref "J2") (pin "2") (pinfunction "2_2") (pintype "bidirectional"))
      (node (ref "J2") (pin "G$1") (pinfunction "SHIELD_G$1") (pintype "bidirectional"))
      (node (ref "J2") (pin "G$2") (pinfunction "SHIELD_G$2") (pintype "bidirectional"))
      (node (ref "J2") (pin "G$3") (pinfunction "SHIELD_G$3") (pintype "bidirectional"))
      (node (ref "J4") (pin "12") (pinfunction "12_12") (pintype "passive"))
      (node (ref "J5") (pin "5") (pinfunction "5_5") (pintype "passive"))
      (node (ref "J5") (pin "6") (pinfunction "6_6") (pintype "passive"))
      (node (ref "L1") (pin "2") (pinfunction "2_2") (pintype "passive"))
      (node (ref "Q1") (pin "1") (pinfunction "S_1") (pintype "passive"))
      (node (ref "Q2") (pin "1") (pinfunction "S_1") (pintype "passive"))
      (node (ref "R11") (pin "2") (pinfunction "2_2") (pintype "passive"))
      (node (ref "R17") (pin "1") (pinfunction "1_1") (pintype "passive"))
      (node (ref "R5") (pin "1") (pinfunction "1_1") (pintype "passive"))
      (node (ref "R6") (pin "1") (pinfunction "1_1") (pintype "passive"))
      (node (ref "R7") (pin "1") (pinfunction "1_1") (pintype "passive"))
      (node (ref "U1") (pin "1") (pinfunction "OC_1") (pintype "input"))
      (node (ref "U15") (pin "1") (pinfunction "G_1") (pintype "input"))
      (node (ref "U15") (pin "19") (pinfunction "G_19") (pintype "input"))
      (node (ref "U16") (pin "1") (pinfunction "DIR_1") (pintype "input"))
      (node (ref "U17") (pin "1") (pinfunction "GND_1") (pintype "input"))
      (node (ref "U17") (pin "20") (pinfunction "GND/DAC_20") (pintype "input"))
      (node (ref "U18") (pin "1") (pinfunction "GND1_1") (pintype "input"))
      (node (ref "U18") (pin "24") (pinfunction "GND2_24") (pintype "input"))
      (node (ref "U3") (pin "1") (pinfunction "OC_1") (pintype "input"))
      (node (ref "U4") (pin "1") (pinfunction "OC_1") (pintype "input"))
      (node (ref "U7") (pin "5") (pinfunction "G2B_5") (pintype "input"))
      (node (ref "U8") (pin "1") (pinfunction "OC_1") (pintype "input"))
      (node (ref "Y1") (pin "4") (pinfunction "GND_4") (pintype "power_in"))
    )
    (net (code "68") (name "ID0") (class "Default")
      (node (ref "U12") (pin "2") (pinfunction "A1_2") (pintype "input"))
    )
    (net (code "69") (name "ID1") (class "Default")
      (node (ref "U12") (pin "17") (pinfunction "A4_17") (pintype "input"))
    )
    (net (code "70") (name "ID2") (class "Default")
      (node (ref "U12") (pin "4") (pinfunction "A2_4") (pintype "input"))
    )
    (net (code "71") (name "ID3") (class "Default")
      (node (ref "U12") (pin "15") (pinfunction "A3_15") (pintype "input"))
    )
    (net (code "72") (name "ID4") (class "Default")
      (node (ref "U12") (pin "6") (pinfunction "A3_6") (pintype "input"))
    )
    (net (code "73") (name "ID5") (class "Default")
      (node (ref "U12") (pin "13") (pinfunction "A2_13") (pintype "input"))
    )
    (net (code "74") (name "ID6") (class "Default")
      (node (ref "U12") (pin "8") (pinfunction "A4_8") (pintype "input"))
    )
    (net (code "75") (name "ID7") (class "Default")
      (node (ref "U12") (pin "11") (pinfunction "A1_11") (pintype "input"))
    )
    (net (code "76") (name "NTSC_SC") (class "Default")
      (node (ref "R9") (pin "1") (pinfunction "1_1") (pintype "passive"))
      (node (ref "U17") (pin "8") (pinfunction "CPUCLK/~{VDS}_8") (pintype "output"))
    )
    (net (code "77") (name "Net-(C19-1)") (class "Default")
      (node (ref "C19") (pin "P$1") (pinfunction "1_P$1") (pintype "passive"))
      (node (ref "U17") (pin "33") (pinfunction "VBB_33") (pintype "output"))
    )
    (net (code "78") (name "Net-(C21-1)") (class "Default")
      (node (ref "C21") (pin "P$1") (pinfunction "1_P$1") (pintype "passive"))
      (node (ref "U17") (pin "64") (pinfunction "XTAL2_64") (pintype "input"))
      (node (ref "Y2") (pin "1") (pinfunction "1_1") (pintype "passive"))
    )
    (net (code "79") (name "Net-(C22-1)") (class "Default")
      (node (ref "C22") (pin "P$1") (pinfunction "1_P$1") (pintype "passive"))
      (node (ref "U17") (pin "63") (pinfunction "XTAL1_63") (pintype "input"))
      (node (ref "Y2") (pin "2") (pinfunction "2_2") (pintype "passive"))
    )
    (net (code "80") (name "Net-(C25-2)") (class "Default")
      (node (ref "C25") (pin "P$2") (pinfunction "2_P$2") (pintype "passive"))
      (node (ref "U18") (pin "2") (pinfunction "RIN_2") (pintype "input"))
    )
    (net (code "81") (name "Net-(C26-2)") (class "Default")
      (node (ref "C26") (pin "P$2") (pinfunction "2_P$2") (pintype "passive"))
      (node (ref "U18") (pin "3") (pinfunction "GIN_3") (pintype "input"))
    )
    (net (code "82") (name "Net-(C27-2)") (class "Default")
      (node (ref "C27") (pin "P$2") (pinfunction "2_P$2") (pintype "passive"))
      (node (ref "U18") (pin "4") (pinfunction "BIN_4") (pintype "input"))
    )
    (net (code "83") (name "Net-(C29-1)") (class "Default")
      (node (ref "C29") (pin "P$1") (pinfunction "1_P$1") (pintype "passive"))
      (node (ref "R12") (pin "2") (pinfunction "2_2") (pintype "passive"))
      (node (ref "U18") (pin "10") (pinfunction "SYNCIN_10") (pintype "input"))
    )
    (net (code "84") (name "Net-(C34-1)") (class "Default")
      (node (ref "C34") (pin "P$1") (pinfunction "1_P$1") (pintype "passive"))
      (node (ref "R13") (pin "2") (pinfunction "2_2") (pintype "passive"))
      (node (ref "U18") (pin "17") (pinfunction "YTRAP_17") (pintype "output"))
    )
    (net (code "85") (name "Net-(C34-2)") (class "Default")
      (node (ref "C34") (pin "P$2") (pinfunction "2_P$2") (pintype "passive"))
      (node (ref "L1") (pin "1") (pinfunction "1_1") (pintype "passive"))
    )
    (net (code "86") (name "Net-(C35-Pad+)") (class "Default")
      (node (ref "C35") (pin "+") (pinfunction "+_+") (pintype "passive"))
      (node (ref "R14") (pin "2") (pinfunction "2_2") (pintype "passive"))
    )
    (net (code "87") (name "Net-(C35-Pad-)") (class "Default")
      (node (ref "C35") (pin "-") (pinfunction "-_-") (pintype "passive"))
      (node (ref "J2") (pin "3") (pinfunction "3_3") (pintype "bidirectional"))
    )
    (net (code "88") (name "Net-(C36-Pad+)") (class "Default")
      (node (ref "C36") (pin "+") (pinfunction "+_+") (pintype "passive"))
      (node (ref "R15") (pin "2") (pinfunction "2_2") (pintype "passive"))
    )
    (net (code "89") (name "Net-(C36-Pad-)") (class "Default")
      (node (ref "C36") (pin "-") (pinfunction "-_-") (pintype "passive"))
      (node (ref "J2") (pin "4") (pinfunction "4_4") (pintype "bidirectional"))
    )
    (net (code "90") (name "Net-(C37-Pad+)") (class "Default")
      (node (ref "C37") (pin "+") (pinfunction "+_+") (pintype "passive"))
      (node (ref "R16") (pin "2") (pinfunction "2_2") (pintype "passive"))
      (node (ref "R17") (pin "2") (pinfunction "2_2") (pintype "passive"))
    )
    (net (code "91") (name "Net-(C37-Pad-)") (class "Default")
      (node (ref "C37") (pin "-") (pinfunction "-_-") (pintype "passive"))
      (node (ref "J1") (pin "TIP") (pinfunction "TIP_TIP") (pintype "bidirectional"))
    )
    (net (code "92") (name "Net-(CE1-D0)") (class "Default")
      (node (ref "CE1") (pin "43") (pinfunction "D0_43") (pintype "bidirectional"))
      (node (ref "U14") (pin "2") (pinfunction "1D_2") (pintype "input"))
      (node (ref "U16") (pin "2") (pinfunction "A1_2") (pintype "bidirectional"))
    )
    (net (code "93") (name "Net-(CE1-D1)") (class "Default")
      (node (ref "CE1") (pin "44") (pinfunction "D1_44") (pintype "bidirectional"))
      (node (ref "U14") (pin "3") (pinfunction "2D_3") (pintype "input"))
      (node (ref "U16") (pin "3") (pinfunction "A2_3") (pintype "bidirectional"))
    )
    (net (code "94") (name "Net-(CE1-D2)") (class "Default")
      (node (ref "CE1") (pin "45") (pinfunction "D2_45") (pintype "bidirectional"))
      (node (ref "U14") (pin "4") (pinfunction "3D_4") (pintype "input"))
      (node (ref "U16") (pin "4") (pinfunction "A3_4") (pintype "bidirectional"))
    )
    (net (code "95") (name "Net-(CE1-D3)") (class "Default")
      (node (ref "CE1") (pin "46") (pinfunction "D3_46") (pintype "bidirectional"))
      (node (ref "U14") (pin "5") (pinfunction "4D_5") (pintype "input"))
      (node (ref "U16") (pin "5") (pinfunction "A4_5") (pintype "bidirectional"))
    )
    (net (code "96") (name "Net-(CE1-D4)") (class "Default")
      (node (ref "CE1") (pin "47") (pinfunction "D4_47") (pintype "bidirectional"))
      (node (ref "U14") (pin "6") (pinfunction "5D_6") (pintype "input"))
      (node (ref "U16") (pin "6") (pinfunction "A5_6") (pintype "bidirectional"))
    )
    (net (code "97") (name "Net-(CE1-D5)") (class "Default")
      (node (ref "CE1") (pin "48") (pinfunction "D5_48") (pintype "bidirectional"))
      (node (ref "U14") (pin "7") (pinfunction "6D_7") (pintype "input"))
      (node (ref "U16") (pin "7") (pinfunction "A6_7") (pintype "bidirectional"))
    )
    (net (code "98") (name "Net-(CE1-D6)") (class "Default")
      (node (ref "CE1") (pin "49") (pinfunction "D6_49") (pintype "bidirectional"))
      (node (ref "U14") (pin "8") (pinfunction "7D_8") (pintype "input"))
      (node (ref "U16") (pin "8") (pinfunction "A7_8") (pintype "bidirectional"))
    )
    (net (code "99") (name "Net-(CE1-D7)") (class "Default")
      (node (ref "CE1") (pin "50") (pinfunction "D7_50") (pintype "bidirectional"))
      (node (ref "U14") (pin "9") (pinfunction "8D_9") (pintype "input"))
      (node (ref "U16") (pin "9") (pinfunction "A8_9") (pintype "bidirectional"))
    )
    (net (code "100") (name "Net-(CE1-~{IRQX})") (class "Default")
      (node (ref "CE1") (pin "52") (pinfunction "~{IRQX}_52") (pintype "bidirectional"))
      (node (ref "JP3") (pin "1") (pinfunction "1_1") (pintype "passive"))
    )
    (net (code "101") (name "Net-(CE1-~{NMI})") (class "Default")
      (node (ref "CE1") (pin "61") (pinfunction "~{NMI}_61") (pintype "bidirectional"))
      (node (ref "JP3") (pin "3") (pinfunction "3_3") (pintype "passive"))
    )
    (net (code "102") (name "Net-(Q1-D)") (class "Default")
      (node (ref "JP2") (pin "1") (pinfunction "1_1") (pintype "passive"))
      (node (ref "Q1") (pin "3") (pinfunction "D_3") (pintype "passive"))
    )
    (net (code "103") (name "Net-(Q1-G)") (class "Default")
      (node (ref "Q1") (pin "2") (pinfunction "G_2") (pintype "passive"))
      (node (ref "R3") (pin "2") (pinfunction "2_2") (pintype "passive"))
    )
    (net (code "104") (name "Net-(Q2-D)") (class "Default")
      (node (ref "JP3") (pin "2") (pinfunction "2_2") (pintype "passive"))
      (node (ref "Q2") (pin "3") (pinfunction "D_3") (pintype "passive"))
    )
    (net (code "105") (name "Net-(Q2-G)") (class "Default")
      (node (ref "Q2") (pin "2") (pinfunction "G_2") (pintype "passive"))
      (node (ref "R4") (pin "2") (pinfunction "2_2") (pintype "passive"))
    )
    (net (code "106") (name "Net-(U1A-6Q)") (class "Default")
      (node (ref "U1") (pin "14") (pinfunction "6Q_14") (pintype "tri_state"))
      (node (ref "U2") (pin "1") (pinfunction "A18_1") (pintype "input"))
    )
    (net (code "107") (name "Net-(U1A-7Q)") (class "Default")
      (node (ref "U1") (pin "13") (pinfunction "7Q_13") (pintype "tri_state"))
      (node (ref "U2") (pin "2") (pinfunction "A16_2") (pintype "input"))
    )
    (net (code "108") (name "Net-(U1A-8Q)") (class "Default")
      (node (ref "U1") (pin "12") (pinfunction "8Q_12") (pintype "tri_state"))
      (node (ref "U2") (pin "30") (pinfunction "A17_30") (pintype "input"))
    )
    (net (code "109") (name "Net-(U1A-CLK)") (class "Default")
      (node (ref "U1") (pin "11") (pinfunction "CLK_11") (pintype "input"))
      (node (ref "U4") (pin "11") (pinfunction "CLK_11") (pintype "input"))
      (node (ref "U5") (pin "1") (pinfunction "I_1") (pintype "input"))
      (node (ref "U6") (pin "12") (pinfunction "O_12") (pintype "output"))
    )
    (net (code "110") (name "Net-(U2A-A0)") (class "Default")
      (node (ref "U2") (pin "12") (pinfunction "A0_12") (pintype "input"))
      (node (ref "U4") (pin "12") (pinfunction "8Q_12") (pintype "tri_state"))
    )
    (net (code "111") (name "Net-(U2A-A1)") (class "Default")
      (node (ref "U2") (pin "11") (pinfunction "A1_11") (pintype "input"))
      (node (ref "U4") (pin "13") (pinfunction "7Q_13") (pintype "tri_state"))
    )
    (net (code "112") (name "Net-(U2A-A2)") (class "Default")
      (node (ref "U2") (pin "10") (pinfunction "A2_10") (pintype "input"))
      (node (ref "U4") (pin "14") (pinfunction "6Q_14") (pintype "tri_state"))
    )
    (net (code "113") (name "Net-(U2A-A3)") (class "Default")
      (node (ref "U2") (pin "9") (pinfunction "A3_9") (pintype "input"))
      (node (ref "U4") (pin "15") (pinfunction "5Q_15") (pintype "tri_state"))
    )
    (net (code "114") (name "Net-(U2A-A4)") (class "Default")
      (node (ref "U2") (pin "8") (pinfunction "A4_8") (pintype "input"))
      (node (ref "U4") (pin "16") (pinfunction "4Q_16") (pintype "tri_state"))
    )
    (net (code "115") (name "Net-(U2A-A5)") (class "Default")
      (node (ref "U2") (pin "7") (pinfunction "A5_7") (pintype "input"))
      (node (ref "U4") (pin "17") (pinfunction "3Q_17") (pintype "tri_state"))
    )
    (net (code "116") (name "Net-(U2A-A6)") (class "Default")
      (node (ref "U2") (pin "6") (pinfunction "A6_6") (pintype "input"))
      (node (ref "U4") (pin "18") (pinfunction "2Q_18") (pintype "tri_state"))
    )
    (net (code "117") (name "Net-(U2A-A7)") (class "Default")
      (node (ref "U2") (pin "5") (pinfunction "A7_5") (pintype "input"))
      (node (ref "U4") (pin "19") (pinfunction "1Q_19") (pintype "tri_state"))
    )
    (net (code "118") (name "Net-(U2A-A8)") (class "Default")
      (node (ref "U2") (pin "27") (pinfunction "A8_27") (pintype "input"))
      (node (ref "U3") (pin "17") (pinfunction "3Q_17") (pintype "tri_state"))
    )
    (net (code "119") (name "Net-(U2A-A9)") (class "Default")
      (node (ref "U2") (pin "26") (pinfunction "A9_26") (pintype "input"))
      (node (ref "U3") (pin "14") (pinfunction "6Q_14") (pintype "tri_state"))
    )
    (net (code "120") (name "Net-(U2A-A10)") (class "Default")
      (node (ref "U2") (pin "23") (pinfunction "A10_23") (pintype "input"))
      (node (ref "U3") (pin "12") (pinfunction "8Q_12") (pintype "tri_state"))
    )
    (net (code "121") (name "Net-(U2A-A11)") (class "Default")
      (node (ref "U2") (pin "25") (pinfunction "A11_25") (pintype "input"))
      (node (ref "U3") (pin "13") (pinfunction "7Q_13") (pintype "tri_state"))
    )
    (net (code "122") (name "Net-(U2A-A12)") (class "Default")
      (node (ref "U2") (pin "4") (pinfunction "A12_4") (pintype "input"))
      (node (ref "U3") (pin "15") (pinfunction "5Q_15") (pintype "tri_state"))
    )
    (net (code "123") (name "Net-(U2A-A13)") (class "Default")
      (node (ref "U2") (pin "28") (pinfunction "A13_28") (pintype "input"))
      (node (ref "U3") (pin "18") (pinfunction "2Q_18") (pintype "tri_state"))
    )
    (net (code "124") (name "Net-(U2A-A14)") (class "Default")
      (node (ref "U2") (pin "3") (pinfunction "A14_3") (pintype "input"))
      (node (ref "U3") (pin "16") (pinfunction "4Q_16") (pintype "tri_state"))
    )
    (net (code "125") (name "Net-(U2A-A15)") (class "Default")
      (node (ref "U2") (pin "31") (pinfunction "A15_31") (pintype "input"))
      (node (ref "U3") (pin "19") (pinfunction "1Q_19") (pintype "tri_state"))
    )
    (net (code "126") (name "Net-(U2A-~{CE})") (class "Default")
      (node (ref "U2") (pin "22") (pinfunction "~{CE}_22") (pintype "input"))
      (node (ref "U5") (pin "6") (pinfunction "O_6") (pintype "output"))
    )
    (net (code "127") (name "Net-(U2A-~{OE})") (class "Default")
      (node (ref "U2") (pin "24") (pinfunction "~{OE}_24") (pintype "input"))
      (node (ref "U5") (pin "10") (pinfunction "O_10") (pintype "output"))
    )
    (net (code "128") (name "Net-(U3A-CLK)") (class "Default")
      (node (ref "U3") (pin "11") (pinfunction "CLK_11") (pintype "input"))
      (node (ref "U5") (pin "8") (pinfunction "O_8") (pintype "output"))
    )
    (net (code "129") (name "Net-(U5A-O)") (class "Default")
      (node (ref "U5") (pin "2") (pinfunction "O_2") (pintype "output"))
      (node (ref "U5") (pin "3") (pinfunction "I_3") (pintype "input"))
    )
    (net (code "130") (name "Net-(U5B-O)") (class "Default")
      (node (ref "U5") (pin "4") (pinfunction "O_4") (pintype "output"))
      (node (ref "U5") (pin "5") (pinfunction "I_5") (pintype "input"))
    )
    (net (code "131") (name "Net-(U6B-I2)") (class "Default")
      (node (ref "U6") (pin "5") (pinfunction "I2_5") (pintype "input"))
      (node (ref "U9") (pin "1") (pinfunction "CLR_1") (pintype "input"))
      (node (ref "U9") (pin "8") (pinfunction "~{Q}_8") (pintype "output"))
    )
    (net (code "132") (name "Net-(U6B-O)") (class "Default")
      (node (ref "R3") (pin "1") (pinfunction "1_1") (pintype "passive"))
      (node (ref "U6") (pin "6") (pinfunction "O_6") (pintype "output"))
    )
    (net (code "133") (name "Net-(U9A-CLK)") (class "Default")
      (node (ref "JP1") (pin "2") (pinfunction "2_2") (pintype "passive"))
      (node (ref "R1") (pin "1") (pinfunction "1_1") (pintype "passive"))
      (node (ref "U9") (pin "3") (pinfunction "CLK_3") (pintype "input"))
    )
    (net (code "134") (name "Net-(U10A-O)") (class "Default")
      (node (ref "U10") (pin "11") (pinfunction "I_11") (pintype "input"))
      (node (ref "U10") (pin "12") (pinfunction "O_12") (pintype "output"))
    )
    (net (code "135") (name "Net-(U10B-O)") (class "Default")
      (node (ref "U10") (pin "10") (pinfunction "O_10") (pintype "output"))
      (node (ref "U9") (pin "4") (pinfunction "PRE_4") (pintype "input"))
    )
    (net (code "136") (name "Net-(U10C-O)") (class "Default")
      (node (ref "R4") (pin "1") (pinfunction "1_1") (pintype "passive"))
      (node (ref "U10") (pin "8") (pinfunction "O_8") (pintype "output"))
    )
    (net (code "137") (name "Net-(U10D-O)") (class "Default")
      (node (ref "U10") (pin "2") (pinfunction "O_2") (pintype "output"))
      (node (ref "U10") (pin "3") (pinfunction "I_3") (pintype "input"))
    )
    (net (code "138") (name "Net-(U11A-O)") (class "Default")
      (node (ref "U11") (pin "2") (pinfunction "O_2") (pintype "output"))
      (node (ref "U14") (pin "11") (pinfunction "CLK_11") (pintype "input"))
    )
    (net (code "139") (name "Net-(U11D-I)") (class "Default")
      (node (ref "U11") (pin "9") (pinfunction "I_9") (pintype "input"))
      (node (ref "U9") (pin "12") (pinfunction "D_12") (pintype "input"))
      (node (ref "U9") (pin "5") (pinfunction "Q_5") (pintype "output"))
    )
    (net (code "140") (name "Net-(U11D-O)") (class "Default")
      (node (ref "U11") (pin "8") (pinfunction "O_8") (pintype "output"))
      (node (ref "U6") (pin "4") (pinfunction "I1_4") (pintype "input"))
    )
    (net (code "141") (name "Net-(U11E-O)") (class "Default")
      (node (ref "JP1") (pin "1") (pinfunction "1_1") (pintype "passive"))
      (node (ref "U11") (pin "10") (pinfunction "O_10") (pintype "output"))
    )
    (net (code "142") (name "Net-(U13C-O)") (class "Default")
      (node (ref "U13") (pin "8") (pinfunction "O_8") (pintype "output"))
      (node (ref "U14") (pin "1") (pinfunction "OC_1") (pintype "input"))
    )
    (net (code "143") (name "Net-(U13D-O)") (class "Default")
      (node (ref "U13") (pin "11") (pinfunction "O_11") (pintype "output"))
      (node (ref "U16") (pin "19") (pinfunction "G_19") (pintype "input"))
    )
    (net (code "144") (name "Net-(U17-MODE0)") (class "Default")
      (node (ref "U17") (pin "29") (pinfunction "MODE0_29") (pintype "input"))
      (node (ref "U8") (pin "2") (pinfunction "1Q_2") (pintype "tri_state"))
    )
    (net (code "145") (name "Net-(U17-MODE1)") (class "Default")
      (node (ref "U17") (pin "28") (pinfunction "MODE1_28") (pintype "input"))
      (node (ref "U8") (pin "5") (pinfunction "2Q_5") (pintype "tri_state"))
    )
    (net (code "146") (name "Net-(U18-COUT)") (class "Default")
      (node (ref "R15") (pin "1") (pinfunction "1_1") (pintype "passive"))
      (node (ref "U18") (pin "15") (pinfunction "COUT_15") (pintype "output"))
    )
    (net (code "147") (name "Net-(U18-CVOUT)") (class "Default")
      (node (ref "R16") (pin "1") (pinfunction "1_1") (pintype "passive"))
      (node (ref "U18") (pin "20") (pinfunction "CVOUT_20") (pintype "output"))
    )
    (net (code "148") (name "Net-(U18-NPIN)") (class "Default")
      (node (ref "R11") (pin "1") (pinfunction "1_1") (pintype "passive"))
      (node (ref "R8") (pin "1") (pinfunction "1_1") (pintype "passive"))
      (node (ref "U18") (pin "7") (pinfunction "NPIN_7") (pintype "input"))
    )
    (net (code "149") (name "Net-(U18-YOUT)") (class "Default")
      (node (ref "R14") (pin "1") (pinfunction "1_1") (pintype "passive"))
      (node (ref "U18") (pin "16") (pinfunction "YOUT_16") (pintype "output"))
    )
    (net (code "150") (name "PAL_SC") (class "Default")
      (node (ref "R10") (pin "1") (pinfunction "1_1") (pintype "passive"))
      (node (ref "U9") (pin "11") (pinfunction "CLK_11") (pintype "input"))
      (node (ref "Y1") (pin "5") (pinfunction "FO_5") (pintype "output"))
    )
    (net (code "151") (name "R") (class "Default")
      (node (ref "C25") (pin "P$1") (pinfunction "1_P$1") (pintype "passive"))
      (node (ref "J5") (pin "2") (pinfunction "2_2") (pintype "passive"))
      (node (ref "R5") (pin "2") (pinfunction "2_2") (pintype "passive"))
      (node (ref "U17") (pin "23") (pinfunction "R_23") (pintype "output"))
    )
    (net (code "152") (name "SC") (class "Default")
      (node (ref "C28") (pin "P$1") (pinfunction "1_P$1") (pintype "passive"))
      (node (ref "J5") (pin "7") (pinfunction "7_7") (pintype "passive"))
      (node (ref "R10") (pin "2") (pinfunction "2_2") (pintype "passive"))
      (node (ref "R9") (pin "2") (pinfunction "2_2") (pintype "passive"))
      (node (ref "U18") (pin "6") (pinfunction "SCIN_6") (pintype "input"))
    )
    (net (code "153") (name "VA0") (class "Default")
      (node (ref "U17") (pin "49") (pinfunction "AD0_49") (pintype "output"))
      (node (ref "U3") (pin "2") (pinfunction "1D_2") (pintype "input"))
      (node (ref "U4") (pin "9") (pinfunction "8D_9") (pintype "input"))
    )
    (net (code "154") (name "VA1") (class "Default")
      (node (ref "U17") (pin "50") (pinfunction "AD1_50") (pintype "output"))
      (node (ref "U3") (pin "3") (pinfunction "2D_3") (pintype "input"))
      (node (ref "U4") (pin "8") (pinfunction "7D_8") (pintype "input"))
    )
    (net (code "155") (name "VA2") (class "Default")
      (node (ref "U17") (pin "51") (pinfunction "AD2_51") (pintype "output"))
      (node (ref "U3") (pin "4") (pinfunction "3D_4") (pintype "input"))
      (node (ref "U4") (pin "7") (pinfunction "6D_7") (pintype "input"))
    )
    (net (code "156") (name "VA3") (class "Default")
      (node (ref "U17") (pin "52") (pinfunction "AD3_52") (pintype "output"))
      (node (ref "U3") (pin "5") (pinfunction "4D_5") (pintype "input"))
      (node (ref "U4") (pin "6") (pinfunction "5D_6") (pintype "input"))
    )
    (net (code "157") (name "VA4") (class "Default")
      (node (ref "U17") (pin "53") (pinfunction "AD4_53") (pintype "output"))
      (node (ref "U3") (pin "6") (pinfunction "5D_6") (pintype "input"))
      (node (ref "U4") (pin "5") (pinfunction "4D_5") (pintype "input"))
    )
    (net (code "158") (name "VA5") (class "Default")
      (node (ref "U17") (pin "54") (pinfunction "AD5_54") (pintype "output"))
      (node (ref "U3") (pin "7") (pinfunction "6D_7") (pintype "input"))
      (node (ref "U4") (pin "4") (pinfunction "3D_4") (pintype "input"))
    )
    (net (code "159") (name "VA6") (class "Default")
      (node (ref "U17") (pin "55") (pinfunction "AD6_55") (pintype "output"))
      (node (ref "U3") (pin "8") (pinfunction "7D_8") (pintype "input"))
      (node (ref "U4") (pin "3") (pinfunction "2D_3") (pintype "input"))
    )
    (net (code "160") (name "VA7") (class "Default")
      (node (ref "U17") (pin "56") (pinfunction "AD7_56") (pintype "output"))
      (node (ref "U3") (pin "9") (pinfunction "8D_9") (pintype "input"))
      (node (ref "U4") (pin "2") (pinfunction "1D_2") (pintype "input"))
    )
    (net (code "161") (name "VCC") (class "Default")
      (node (ref "C1") (pin "P$1") (pinfunction "1_P$1") (pintype "passive"))
      (node (ref "C10") (pin "P$1") (pinfunction "1_P$1") (pintype "passive"))
      (node (ref "C11") (pin "P$1") (pinfunction "1_P$1") (pintype "passive"))
      (node (ref "C12") (pin "P$1") (pinfunction "1_P$1") (pintype "passive"))
      (node (ref "C13") (pin "P$1") (pinfunction "1_P$1") (pintype "passive"))
      (node (ref "C14") (pin "P$1") (pinfunction "1_P$1") (pintype "passive"))
      (node (ref "C15") (pin "P$1") (pinfunction "1_P$1") (pintype "passive"))
      (node (ref "C16") (pin "P$1") (pinfunction "1_P$1") (pintype "passive"))
      (node (ref "C17") (pin "P$1") (pinfunction "1_P$1") (pintype "passive"))
      (node (ref "C18") (pin "P$1") (pinfunction "1_P$1") (pintype "passive"))
      (node (ref "C2") (pin "P$1") (pinfunction "1_P$1") (pintype "passive"))
      (node (ref "C20") (pin "+") (pinfunction "+_+") (pintype "passive"))
      (node (ref "C23") (pin "P$1") (pinfunction "1_P$1") (pintype "passive"))
      (node (ref "C24") (pin "+") (pinfunction "+_+") (pintype "passive"))
      (node (ref "C3") (pin "P$1") (pinfunction "1_P$1") (pintype "passive"))
      (node (ref "C30") (pin "P$1") (pinfunction "1_P$1") (pintype "passive"))
      (node (ref "C31") (pin "P$1") (pinfunction "1_P$1") (pintype "passive"))
      (node (ref "C32") (pin "+") (pinfunction "+_+") (pintype "passive"))
      (node (ref "C33") (pin "+") (pinfunction "+_+") (pintype "passive"))
      (node (ref "C4") (pin "P$1") (pinfunction "1_P$1") (pintype "passive"))
      (node (ref "C5") (pin "P$1") (pinfunction "1_P$1") (pintype "passive"))
      (node (ref "C6") (pin "P$1") (pinfunction "1_P$1") (pintype "passive"))
      (node (ref "C7") (pin "P$1") (pinfunction "1_P$1") (pintype "passive"))
      (node (ref "C8") (pin "P$1") (pinfunction "1_P$1") (pintype "passive"))
      (node (ref "C9") (pin "P$1") (pinfunction "1_P$1") (pintype "passive"))
      (node (ref "CE1") (pin "5") (pinfunction "+5V_5") (pintype "bidirectional"))
      (node (ref "CE1") (pin "6") (pinfunction "+5V_6") (pintype "bidirectional"))
      (node (ref "J5") (pin "4") (pinfunction "4_4") (pintype "passive"))
      (node (ref "R1") (pin "2") (pinfunction "2_2") (pintype "passive"))
      (node (ref "R13") (pin "1") (pinfunction "1_1") (pintype "passive"))
      (node (ref "R18") (pin "2") (pinfunction "2_2") (pintype "passive"))
      (node (ref "R2") (pin "2") (pinfunction "2_2") (pintype "passive"))
      (node (ref "R8") (pin "2") (pinfunction "2_2") (pintype "passive"))
      (node (ref "RN1") (pin "1") (pinfunction "1_1") (pintype "passive"))
      (node (ref "U1") (pin "2") (pinfunction "1D_2") (pintype "input"))
      (node (ref "U1") (pin "3") (pinfunction "2D_3") (pintype "input"))
      (node (ref "U1") (pin "4") (pinfunction "3D_4") (pintype "input"))
      (node (ref "U1") (pin "5") (pinfunction "4D_5") (pintype "input"))
      (node (ref "U1") (pin "6") (pinfunction "5D_6") (pintype "input"))
      (node (ref "U10") (pin "5") (pinfunction "I_5") (pintype "input"))
      (node (ref "U11") (pin "13") (pinfunction "I_13") (pintype "input"))
      (node (ref "U11") (pin "3") (pinfunction "I_3") (pintype "input"))
      (node (ref "U11") (pin "5") (pinfunction "I_5") (pintype "input"))
      (node (ref "U13") (pin "1") (pinfunction "I0_1") (pintype "input"))
      (node (ref "U13") (pin "2") (pinfunction "I1_2") (pintype "input"))
      (node (ref "U13") (pin "4") (pinfunction "I0_4") (pintype "input"))
      (node (ref "U13") (pin "5") (pinfunction "I1_5") (pintype "input"))
      (node (ref "U15") (pin "17") (pinfunction "A4_17") (pintype "input"))
      (node (ref "U15") (pin "4") (pinfunction "A2_4") (pintype "input"))
      (node (ref "U17") (pin "21") (pinfunction "VDD/DAC_21") (pintype "input"))
      (node (ref "U17") (pin "27") (pinfunction "~{HRESET}_27") (pintype "input"))
      (node (ref "U17") (pin "4") (pinfunction "~{VRESET}_4") (pintype "input"))
      (node (ref "U17") (pin "58") (pinfunction "VDD_58") (pintype "input"))
      (node (ref "U18") (pin "12") (pinfunction "VCC1_12") (pintype "input"))
      (node (ref "U18") (pin "19") (pinfunction "VCC2_19") (pintype "input"))
      (node (ref "U5") (pin "13") (pinfunction "I_13") (pintype "input"))
      (node (ref "U6") (pin "10") (pinfunction "I1_10") (pintype "input"))
      (node (ref "U6") (pin "11") (pinfunction "I2_11") (pintype "input"))
      (node (ref "U6") (pin "3") (pinfunction "I0_3") (pintype "input"))
      (node (ref "U6") (pin "9") (pinfunction "I0_9") (pintype "input"))
      (node (ref "U7") (pin "6") (pinfunction "G1_6") (pintype "input"))
      (node (ref "U8") (pin "13") (pinfunction "5D_13") (pintype "input"))
      (node (ref "U8") (pin "14") (pinfunction "6D_14") (pintype "input"))
      (node (ref "U8") (pin "17") (pinfunction "7D_17") (pintype "input"))
      (node (ref "U8") (pin "18") (pinfunction "8D_18") (pintype "input"))
      (node (ref "U8") (pin "8") (pinfunction "4D_8") (pintype "input"))
      (node (ref "U9") (pin "10") (pinfunction "PRE_10") (pintype "input"))
      (node (ref "U9") (pin "2") (pinfunction "D_2") (pintype "input"))
      (node (ref "Y1") (pin "1") (pinfunction "OE_1") (pintype "input"))
      (node (ref "Y1") (pin "8") (pinfunction "VCC_8") (pintype "power_in"))
    )
    (net (code "162") (name "VD0") (class "Default")
      (node (ref "U17") (pin "41") (pinfunction "RD0_41") (pintype "bidirectional"))
      (node (ref "U2") (pin "17") (pinfunction "D3_17") (pintype "tri_state"))
    )
    (net (code "163") (name "VD1") (class "Default")
      (node (ref "U17") (pin "42") (pinfunction "RD1_42") (pintype "bidirectional"))
      (node (ref "U2") (pin "18") (pinfunction "D4_18") (pintype "tri_state"))
    )
    (net (code "164") (name "VD2") (class "Default")
      (node (ref "U17") (pin "43") (pinfunction "RD2_43") (pintype "bidirectional"))
      (node (ref "U2") (pin "19") (pinfunction "D5_19") (pintype "tri_state"))
    )
    (net (code "165") (name "VD3") (class "Default")
      (node (ref "U17") (pin "44") (pinfunction "RD3_44") (pintype "bidirectional"))
      (node (ref "U2") (pin "15") (pinfunction "D2_15") (pintype "tri_state"))
    )
    (net (code "166") (name "VD4") (class "Default")
      (node (ref "U17") (pin "45") (pinfunction "RD4_45") (pintype "bidirectional"))
      (node (ref "U2") (pin "20") (pinfunction "D6_20") (pintype "tri_state"))
    )
    (net (code "167") (name "VD5") (class "Default")
      (node (ref "U17") (pin "46") (pinfunction "RD5_46") (pintype "bidirectional"))
      (node (ref "U2") (pin "14") (pinfunction "D1_14") (pintype "tri_state"))
    )
    (net (code "168") (name "VD6") (class "Default")
      (node (ref "U17") (pin "47") (pinfunction "RD6_47") (pintype "bidirectional"))
      (node (ref "U2") (pin "21") (pinfunction "D7_21") (pintype "tri_state"))
    )
    (net (code "169") (name "VD7") (class "Default")
      (node (ref "U17") (pin "48") (pinfunction "RD7_48") (pintype "bidirectional"))
      (node (ref "U2") (pin "13") (pinfunction "D0_13") (pintype "tri_state"))
    )
    (net (code "170") (name "VR{slash}~{W}") (class "Default")
      (node (ref "U17") (pin "57") (pinfunction "R/~{W}_57") (pintype "output"))
      (node (ref "U2") (pin "29") (pinfunction "~{WE}_29") (pintype "input"))
      (node (ref "U5") (pin "11") (pinfunction "I_11") (pintype "input"))
    )
    (net (code "171") (name "unconnected-(CE1-+3.3V-Pad2)") (class "Default")
      (node (ref "CE1") (pin "2") (pinfunction "+3.3V_2") (pintype "bidirectional"))
    )
    (net (code "172") (name "unconnected-(CE1-+5VSB-Pad8)") (class "Default")
      (node (ref "CE1") (pin "8") (pinfunction "+5VSB_8") (pintype "bidirectional"))
    )
    (net (code "173") (name "unconnected-(CE1-+12V-Pad1)") (class "Default")
      (node (ref "CE1") (pin "1") (pinfunction "+12V_1") (pintype "bidirectional"))
    )
    (net (code "174") (name "unconnected-(CE1--12V-Pad7)") (class "Default")
      (node (ref "CE1") (pin "7") (pinfunction "-12V_7") (pintype "bidirectional"))
    )
    (net (code "175") (name "unconnected-(CE1-A2-Pad25)") (class "Default")
      (node (ref "CE1") (pin "25") (pinfunction "A2_25") (pintype "bidirectional"))
    )
    (net (code "176") (name "unconnected-(CE1-A3-Pad26)") (class "Default")
      (node (ref "CE1") (pin "26") (pinfunction "A3_26") (pintype "bidirectional"))
    )
    (net (code "177") (name "unconnected-(CE1-A4-Pad27)") (class "Default")
      (node (ref "CE1") (pin "27") (pinfunction "A4_27") (pintype "bidirectional"))
    )
    (net (code "178") (name "unconnected-(CE1-A5-Pad28)") (class "Default")
      (node (ref "CE1") (pin "28") (pinfunction "A5_28") (pintype "bidirectional"))
    )
    (net (code "179") (name "unconnected-(CE1-A6-Pad29)") (class "Default")
      (node (ref "CE1") (pin "29") (pinfunction "A6_29") (pintype "bidirectional"))
    )
    (net (code "180") (name "unconnected-(CE1-A8-Pad31)") (class "Default")
      (node (ref "CE1") (pin "31") (pinfunction "A8_31") (pintype "bidirectional"))
    )
    (net (code "181") (name "unconnected-(CE1-A9-Pad32)") (class "Default")
      (node (ref "CE1") (pin "32") (pinfunction "A9_32") (pintype "bidirectional"))
    )
    (net (code "182") (name "unconnected-(CE1-A10-Pad33)") (class "Default")
      (node (ref "CE1") (pin "33") (pinfunction "A10_33") (pintype "bidirectional"))
    )
    (net (code "183") (name "unconnected-(CE1-A11-Pad34)") (class "Default")
      (node (ref "CE1") (pin "34") (pinfunction "A11_34") (pintype "bidirectional"))
    )
    (net (code "184") (name "unconnected-(CE1-A12-Pad35)") (class "Default")
      (node (ref "CE1") (pin "35") (pinfunction "A12_35") (pintype "bidirectional"))
    )
    (net (code "185") (name "unconnected-(CE1-A13-Pad36)") (class "Default")
      (node (ref "CE1") (pin "36") (pinfunction "A13_36") (pintype "bidirectional"))
    )
    (net (code "186") (name "unconnected-(CE1-A14-Pad37)") (class "Default")
      (node (ref "CE1") (pin "37") (pinfunction "A14_37") (pintype "bidirectional"))
    )
    (net (code "187") (name "unconnected-(CE1-A15-Pad38)") (class "Default")
      (node (ref "CE1") (pin "38") (pinfunction "A15_38") (pintype "bidirectional"))
    )
    (net (code "188") (name "unconnected-(CE1-A16-Pad39)") (class "Default")
      (node (ref "CE1") (pin "39") (pinfunction "A16_39") (pintype "bidirectional"))
    )
    (net (code "189") (name "unconnected-(CE1-A17-Pad40)") (class "Default")
      (node (ref "CE1") (pin "40") (pinfunction "A17_40") (pintype "bidirectional"))
    )
    (net (code "190") (name "unconnected-(CE1-A18-Pad41)") (class "Default")
      (node (ref "CE1") (pin "41") (pinfunction "A18_41") (pintype "bidirectional"))
    )
    (net (code "191") (name "unconnected-(CE1-A19-Pad42)") (class "Default")
      (node (ref "CE1") (pin "42") (pinfunction "A19_42") (pintype "bidirectional"))
    )
    (net (code "192") (name "unconnected-(CE1-CLK-Pad15)") (class "Default")
      (node (ref "CE1") (pin "15") (pinfunction "CLK_15") (pintype "bidirectional"))
    )
    (net (code "193") (name "unconnected-(CE1-~{BUSACK}-Pad20)") (class "Default")
      (node (ref "CE1") (pin "20") (pinfunction "~{BUSACK}_20") (pintype "bidirectional"))
    )
    (net (code "194") (name "unconnected-(CE1-~{BUSRQ}-Pad10)") (class "Default")
      (node (ref "CE1") (pin "10") (pinfunction "~{BUSRQ}_10") (pintype "bidirectional"))
    )
    (net (code "195") (name "unconnected-(CE1-~{CBR}-Pad12)") (class "Default")
      (node (ref "CE1") (pin "12") (pinfunction "~{CBR}_12") (pintype "bidirectional"))
    )
    (net (code "196") (name "unconnected-(CE1-~{CINH}-Pad13)") (class "Default")
      (node (ref "CE1") (pin "13") (pinfunction "~{CINH}_13") (pintype "bidirectional"))
    )
    (net (code "197") (name "unconnected-(CE1-~{FETCH}-Pad19)") (class "Default")
      (node (ref "CE1") (pin "19") (pinfunction "~{FETCH}_19") (pintype "bidirectional"))
    )
    (net (code "198") (name "unconnected-(CE1-~{HALT}-Pad17)") (class "Default")
      (node (ref "CE1") (pin "17") (pinfunction "~{HALT}_17") (pintype "bidirectional"))
    )
    (net (code "199") (name "unconnected-(CE1-~{INH}-Pad11)") (class "Default")
      (node (ref "CE1") (pin "11") (pinfunction "~{INH}_11") (pintype "bidirectional"))
    )
    (net (code "200") (name "unconnected-(CE1-~{INT}-Pad51)") (class "Default")
      (node (ref "CE1") (pin "51") (pinfunction "~{INT}_51") (pintype "bidirectional"))
    )
    (net (code "201") (name "unconnected-(CE1-~{IOSEL}-Pad16)") (class "Default")
      (node (ref "CE1") (pin "16") (pinfunction "~{IOSEL}_16") (pintype "bidirectional"))
    )
    (net (code "202") (name "unconnected-(CE1-~{IRQ0}-Pad53)") (class "Default")
      (node (ref "CE1") (pin "53") (pinfunction "~{IRQ0}_53") (pintype "bidirectional"))
    )
    (net (code "203") (name "unconnected-(CE1-~{IRQ1}-Pad54)") (class "Default")
      (node (ref "CE1") (pin "54") (pinfunction "~{IRQ1}_54") (pintype "bidirectional"))
    )
    (net (code "204") (name "unconnected-(CE1-~{IRQ2}-Pad55)") (class "Default")
      (node (ref "CE1") (pin "55") (pinfunction "~{IRQ2}_55") (pintype "bidirectional"))
    )
    (net (code "205") (name "unconnected-(CE1-~{IRQ3}-Pad56)") (class "Default")
      (node (ref "CE1") (pin "56") (pinfunction "~{IRQ3}_56") (pintype "bidirectional"))
    )
    (net (code "206") (name "unconnected-(CE1-~{IRQ4}-Pad57)") (class "Default")
      (node (ref "CE1") (pin "57") (pinfunction "~{IRQ4}_57") (pintype "bidirectional"))
    )
    (net (code "207") (name "unconnected-(CE1-~{IRQ5}-Pad58)") (class "Default")
      (node (ref "CE1") (pin "58") (pinfunction "~{IRQ5}_58") (pintype "bidirectional"))
    )
    (net (code "208") (name "unconnected-(CE1-~{IRQ6}-Pad59)") (class "Default")
      (node (ref "CE1") (pin "59") (pinfunction "~{IRQ6}_59") (pintype "bidirectional"))
    )
    (net (code "209") (name "unconnected-(CE1-~{IRQ7}-Pad60)") (class "Default")
      (node (ref "CE1") (pin "60") (pinfunction "~{IRQ7}_60") (pintype "bidirectional"))
    )
    (net (code "210") (name "unconnected-(J1-PadSHUNT)") (class "Default")
      (node (ref "J1") (pin "SHUNT") (pinfunction "SHUNT_SHUNT") (pintype "bidirectional"))
    )
    (net (code "211") (name "unconnected-(U1A-1Q-Pad19)") (class "Default")
      (node (ref "U1") (pin "19") (pinfunction "1Q_19") (pintype "tri_state"))
    )
    (net (code "212") (name "unconnected-(U1A-2Q-Pad18)") (class "Default")
      (node (ref "U1") (pin "18") (pinfunction "2Q_18") (pintype "tri_state"))
    )
    (net (code "213") (name "unconnected-(U1A-3Q-Pad17)") (class "Default")
      (node (ref "U1") (pin "17") (pinfunction "3Q_17") (pintype "tri_state"))
    )
    (net (code "214") (name "unconnected-(U1A-4Q-Pad16)") (class "Default")
      (node (ref "U1") (pin "16") (pinfunction "4Q_16") (pintype "tri_state"))
    )
    (net (code "215") (name "unconnected-(U1A-5Q-Pad15)") (class "Default")
      (node (ref "U1") (pin "15") (pinfunction "5Q_15") (pintype "tri_state"))
    )
    (net (code "216") (name "unconnected-(U5F-O-Pad12)") (class "Default")
      (node (ref "U5") (pin "12") (pinfunction "O_12") (pintype "output"))
    )
    (net (code "217") (name "unconnected-(U6C-O-Pad8)") (class "Default")
      (node (ref "U6") (pin "8") (pinfunction "O_8") (pintype "output"))
    )
    (net (code "218") (name "unconnected-(U7A-Y0-Pad15)") (class "Default")
      (node (ref "U7") (pin "15") (pinfunction "Y0_15") (pintype "output"))
    )
    (net (code "219") (name "unconnected-(U7A-Y3-Pad12)") (class "Default")
      (node (ref "U7") (pin "12") (pinfunction "Y3_12") (pintype "output"))
    )
    (net (code "220") (name "unconnected-(U7A-Y4-Pad11)") (class "Default")
      (node (ref "U7") (pin "11") (pinfunction "Y4_11") (pintype "output"))
    )
    (net (code "221") (name "unconnected-(U7A-Y5-Pad10)") (class "Default")
      (node (ref "U7") (pin "10") (pinfunction "Y5_10") (pintype "output"))
    )
    (net (code "222") (name "unconnected-(U7A-Y7-Pad7)") (class "Default")
      (node (ref "U7") (pin "7") (pinfunction "Y7_7") (pintype "output"))
    )
    (net (code "223") (name "unconnected-(U8A-3Q-Pad6)") (class "Default")
      (node (ref "U8") (pin "6") (pinfunction "3Q_6") (pintype "tri_state"))
    )
    (net (code "224") (name "unconnected-(U8A-4Q-Pad9)") (class "Default")
      (node (ref "U8") (pin "9") (pinfunction "4Q_9") (pintype "tri_state"))
    )
    (net (code "225") (name "unconnected-(U8A-5Q-Pad12)") (class "Default")
      (node (ref "U8") (pin "12") (pinfunction "5Q_12") (pintype "tri_state"))
    )
    (net (code "226") (name "unconnected-(U8A-6Q-Pad15)") (class "Default")
      (node (ref "U8") (pin "15") (pinfunction "6Q_15") (pintype "tri_state"))
    )
    (net (code "227") (name "unconnected-(U8A-7Q-Pad16)") (class "Default")
      (node (ref "U8") (pin "16") (pinfunction "7Q_16") (pintype "tri_state"))
    )
    (net (code "228") (name "unconnected-(U8A-8Q-Pad19)") (class "Default")
      (node (ref "U8") (pin "19") (pinfunction "8Q_19") (pintype "tri_state"))
    )
    (net (code "229") (name "unconnected-(U9A-~{Q}-Pad6)") (class "Default")
      (node (ref "U9") (pin "6") (pinfunction "~{Q}_6") (pintype "output"))
    )
    (net (code "230") (name "unconnected-(U9B-Q-Pad9)") (class "Default")
      (node (ref "U9") (pin "9") (pinfunction "Q_9") (pintype "output"))
    )
    (net (code "231") (name "unconnected-(U10F-O-Pad6)") (class "Default")
      (node (ref "U10") (pin "6") (pinfunction "O_6") (pintype "output"))
    )
    (net (code "232") (name "unconnected-(U11B-O-Pad4)") (class "Default")
      (node (ref "U11") (pin "4") (pinfunction "O_4") (pintype "output"))
    )
    (net (code "233") (name "unconnected-(U11C-O-Pad6)") (class "Default")
      (node (ref "U11") (pin "6") (pinfunction "O_6") (pintype "output"))
    )
    (net (code "234") (name "unconnected-(U11F-O-Pad12)") (class "Default")
      (node (ref "U11") (pin "12") (pinfunction "O_12") (pintype "output"))
    )
    (net (code "235") (name "unconnected-(U13A-O-Pad3)") (class "Default")
      (node (ref "U13") (pin "3") (pinfunction "O_3") (pintype "output"))
    )
    (net (code "236") (name "unconnected-(U13B-O-Pad6)") (class "Default")
      (node (ref "U13") (pin "6") (pinfunction "O_6") (pintype "output"))
    )
    (net (code "237") (name "unconnected-(U15A-Y2-Pad16)") (class "Default")
      (node (ref "U15") (pin "16") (pinfunction "Y2_16") (pintype "tri_state"))
    )
    (net (code "238") (name "unconnected-(U15B-Y4-Pad3)") (class "Default")
      (node (ref "U15") (pin "3") (pinfunction "Y4_3") (pintype "tri_state"))
    )
    (net (code "239") (name "unconnected-(U17-BLEO-Pad7)") (class "Default")
      (node (ref "U17") (pin "7") (pinfunction "BLEO_7") (pintype "output"))
    )
    (net (code "240") (name "unconnected-(U17-~{HSYNC}-Pad5)") (class "Default")
      (node (ref "U17") (pin "5") (pinfunction "~{HSYNC}_5") (pintype "output"))
    )
    (net (code "241") (name "unconnected-(U17-~{YS}-Pad10)") (class "Default")
      (node (ref "U17") (pin "10") (pinfunction "~{YS}_10") (pintype "output"))
    )
    (net (code "242") (name "unconnected-(U18-BFOUT-Pad8)") (class "Default")
      (node (ref "U18") (pin "8") (pinfunction "BFOUT_8") (pintype "output"))
    )
    (net (code "243") (name "unconnected-(U18-BOUT-Pad21)") (class "Default")
      (node (ref "U18") (pin "21") (pinfunction "BOUT_21") (pintype "output"))
    )
    (net (code "244") (name "unconnected-(U18-GOUT-Pad22)") (class "Default")
      (node (ref "U18") (pin "22") (pinfunction "GOUT_22") (pintype "output"))
    )
    (net (code "245") (name "unconnected-(U18-ROUT-Pad23)") (class "Default")
      (node (ref "U18") (pin "23") (pinfunction "ROUT_23") (pintype "output"))
    )
    (net (code "246") (name "~{BCSX}") (class "Default")
      (node (ref "CE1") (pin "9") (pinfunction "~{CSX}_9") (pintype "bidirectional"))
      (node (ref "U15") (pin "2") (pinfunction "A1_2") (pintype "input"))
    )
    (net (code "247") (name "~{BRD}") (class "Default")
      (node (ref "CE1") (pin "21") (pinfunction "~{RD}_21") (pintype "bidirectional"))
      (node (ref "U15") (pin "15") (pinfunction "A3_15") (pintype "input"))
    )
    (net (code "248") (name "~{BRST}") (class "Default")
      (node (ref "CE1") (pin "14") (pinfunction "~{RST}_14") (pintype "bidirectional"))
      (node (ref "U10") (pin "1") (pinfunction "I_1") (pintype "input"))
    )
    (net (code "249") (name "~{BWAIT}") (class "Default")
      (node (ref "CE1") (pin "18") (pinfunction "~{WAIT}_18") (pintype "bidirectional"))
      (node (ref "JP2") (pin "2") (pinfunction "2_2") (pintype "passive"))
    )
    (net (code "250") (name "~{BWR}") (class "Default")
      (node (ref "CE1") (pin "22") (pinfunction "~{WR}_22") (pintype "bidirectional"))
      (node (ref "U15") (pin "6") (pinfunction "A3_6") (pintype "input"))
    )
    (net (code "251") (name "~{CSIDR}") (class "Default")
      (node (ref "U12") (pin "1") (pinfunction "G_1") (pintype "input"))
      (node (ref "U12") (pin "19") (pinfunction "G_19") (pintype "input"))
      (node (ref "U7") (pin "9") (pinfunction "Y6_9") (pintype "output"))
    )
    (net (code "252") (name "~{CSVR}") (class "Default")
      (node (ref "U17") (pin "31") (pinfunction "~{CSR}_31") (pintype "input"))
      (node (ref "U7") (pin "13") (pinfunction "Y2_13") (pintype "output"))
    )
    (net (code "253") (name "~{CSVW}") (class "Default")
      (node (ref "U17") (pin "30") (pinfunction "~{CSW}_30") (pintype "input"))
      (node (ref "U7") (pin "14") (pinfunction "Y1_14") (pintype "output"))
    )
    (net (code "254") (name "~{CSX}") (class "Default")
      (node (ref "U11") (pin "11") (pinfunction "I_11") (pintype "input"))
      (node (ref "U13") (pin "13") (pinfunction "I1_13") (pintype "input"))
      (node (ref "U13") (pin "9") (pinfunction "I0_9") (pintype "input"))
      (node (ref "U15") (pin "18") (pinfunction "Y1_18") (pintype "tri_state"))
      (node (ref "U7") (pin "4") (pinfunction "G2A_4") (pintype "input"))
      (node (ref "U8") (pin "11") (pinfunction "ENC_11") (pintype "input"))
    )
    (net (code "255") (name "~{CSYNC}") (class "Default")
      (node (ref "J5") (pin "8") (pinfunction "8_8") (pintype "passive"))
      (node (ref "R12") (pin "1") (pinfunction "1_1") (pintype "passive"))
      (node (ref "U17") (pin "6") (pinfunction "~{CSYNC}_6") (pintype "output"))
    )
    (net (code "256") (name "~{DHCLK}") (class "Default")
      (node (ref "J4") (pin "11") (pinfunction "11_11") (pintype "passive"))
      (node (ref "U17") (pin "2") (pinfunction "~{DHCLK}_2") (pintype "output"))
    )
    (net (code "257") (name "~{DLCLK}") (class "Default")
      (node (ref "J4") (pin "10") (pinfunction "10_10") (pintype "passive"))
      (node (ref "R18") (pin "1") (pinfunction "1_1") (pintype "passive"))
      (node (ref "U17") (pin "3") (pinfunction "~{DLCLK}_3") (pintype "bidirectional"))
    )
    (net (code "258") (name "~{RD}") (class "Default")
      (node (ref "U13") (pin "12") (pinfunction "I0_12") (pintype "input"))
      (node (ref "U15") (pin "5") (pinfunction "Y3_5") (pintype "tri_state"))
      (node (ref "U7") (pin "1") (pinfunction "A_1") (pintype "input"))
    )
    (net (code "259") (name "~{RST}") (class "Default")
      (node (ref "U10") (pin "4") (pinfunction "O_4") (pintype "output"))
      (node (ref "U17") (pin "9") (pinfunction "~{RESET}_9") (pintype "input"))
      (node (ref "U9") (pin "13") (pinfunction "CLR_13") (pintype "input"))
    )
    (net (code "260") (name "~{VCAS0}") (class "Default")
      (node (ref "U1") (pin "7") (pinfunction "6D_7") (pintype "input"))
      (node (ref "U17") (pin "61") (pinfunction "~{CAS0}_61") (pintype "output"))
      (node (ref "U6") (pin "1") (pinfunction "I0_1") (pintype "input"))
    )
    (net (code "261") (name "~{VCAS1}") (class "Default")
      (node (ref "U1") (pin "8") (pinfunction "7D_8") (pintype "input"))
      (node (ref "U17") (pin "60") (pinfunction "~{CAS1}_60") (pintype "output"))
      (node (ref "U6") (pin "13") (pinfunction "I2_13") (pintype "input"))
    )
    (net (code "262") (name "~{VCAS2}") (class "Default")
      (node (ref "U1") (pin "9") (pinfunction "8D_9") (pintype "input"))
      (node (ref "U17") (pin "59") (pinfunction "~{CASX}_59") (pintype "output"))
      (node (ref "U6") (pin "2") (pinfunction "I1_2") (pintype "input"))
    )
    (net (code "263") (name "~{VINT}") (class "Default")
      (node (ref "U10") (pin "9") (pinfunction "I_9") (pintype "input"))
      (node (ref "U17") (pin "25") (pinfunction "~{INT}_25") (pintype "output"))
    )
    (net (code "264") (name "~{VRAS}") (class "Default")
      (node (ref "U17") (pin "62") (pinfunction "~{RAS}_62") (pintype "output"))
      (node (ref "U5") (pin "9") (pinfunction "I_9") (pintype "input"))
    )
    (net (code "265") (name "~{VWAIT}") (class "Default")
      (node (ref "R2") (pin "1") (pinfunction "1_1") (pintype "passive"))
      (node (ref "U10") (pin "13") (pinfunction "I_13") (pintype "input"))
      (node (ref "U17") (pin "26") (pinfunction "~{WAIT}_26") (pintype "output"))
    )
    (net (code "266") (name "~{WR}") (class "Default")
      (node (ref "U11") (pin "1") (pinfunction "I_1") (pintype "input"))
      (node (ref "U13") (pin "10") (pinfunction "I1_10") (pintype "input"))
      (node (ref "U15") (pin "14") (pinfunction "Y3_14") (pintype "tri_state"))
      (node (ref "U7") (pin "2") (pinfunction "B_2") (pintype "input"))
    )
  )
)
